# Seymour.net
KiCad netlist of a schematic drawn in EAGLE
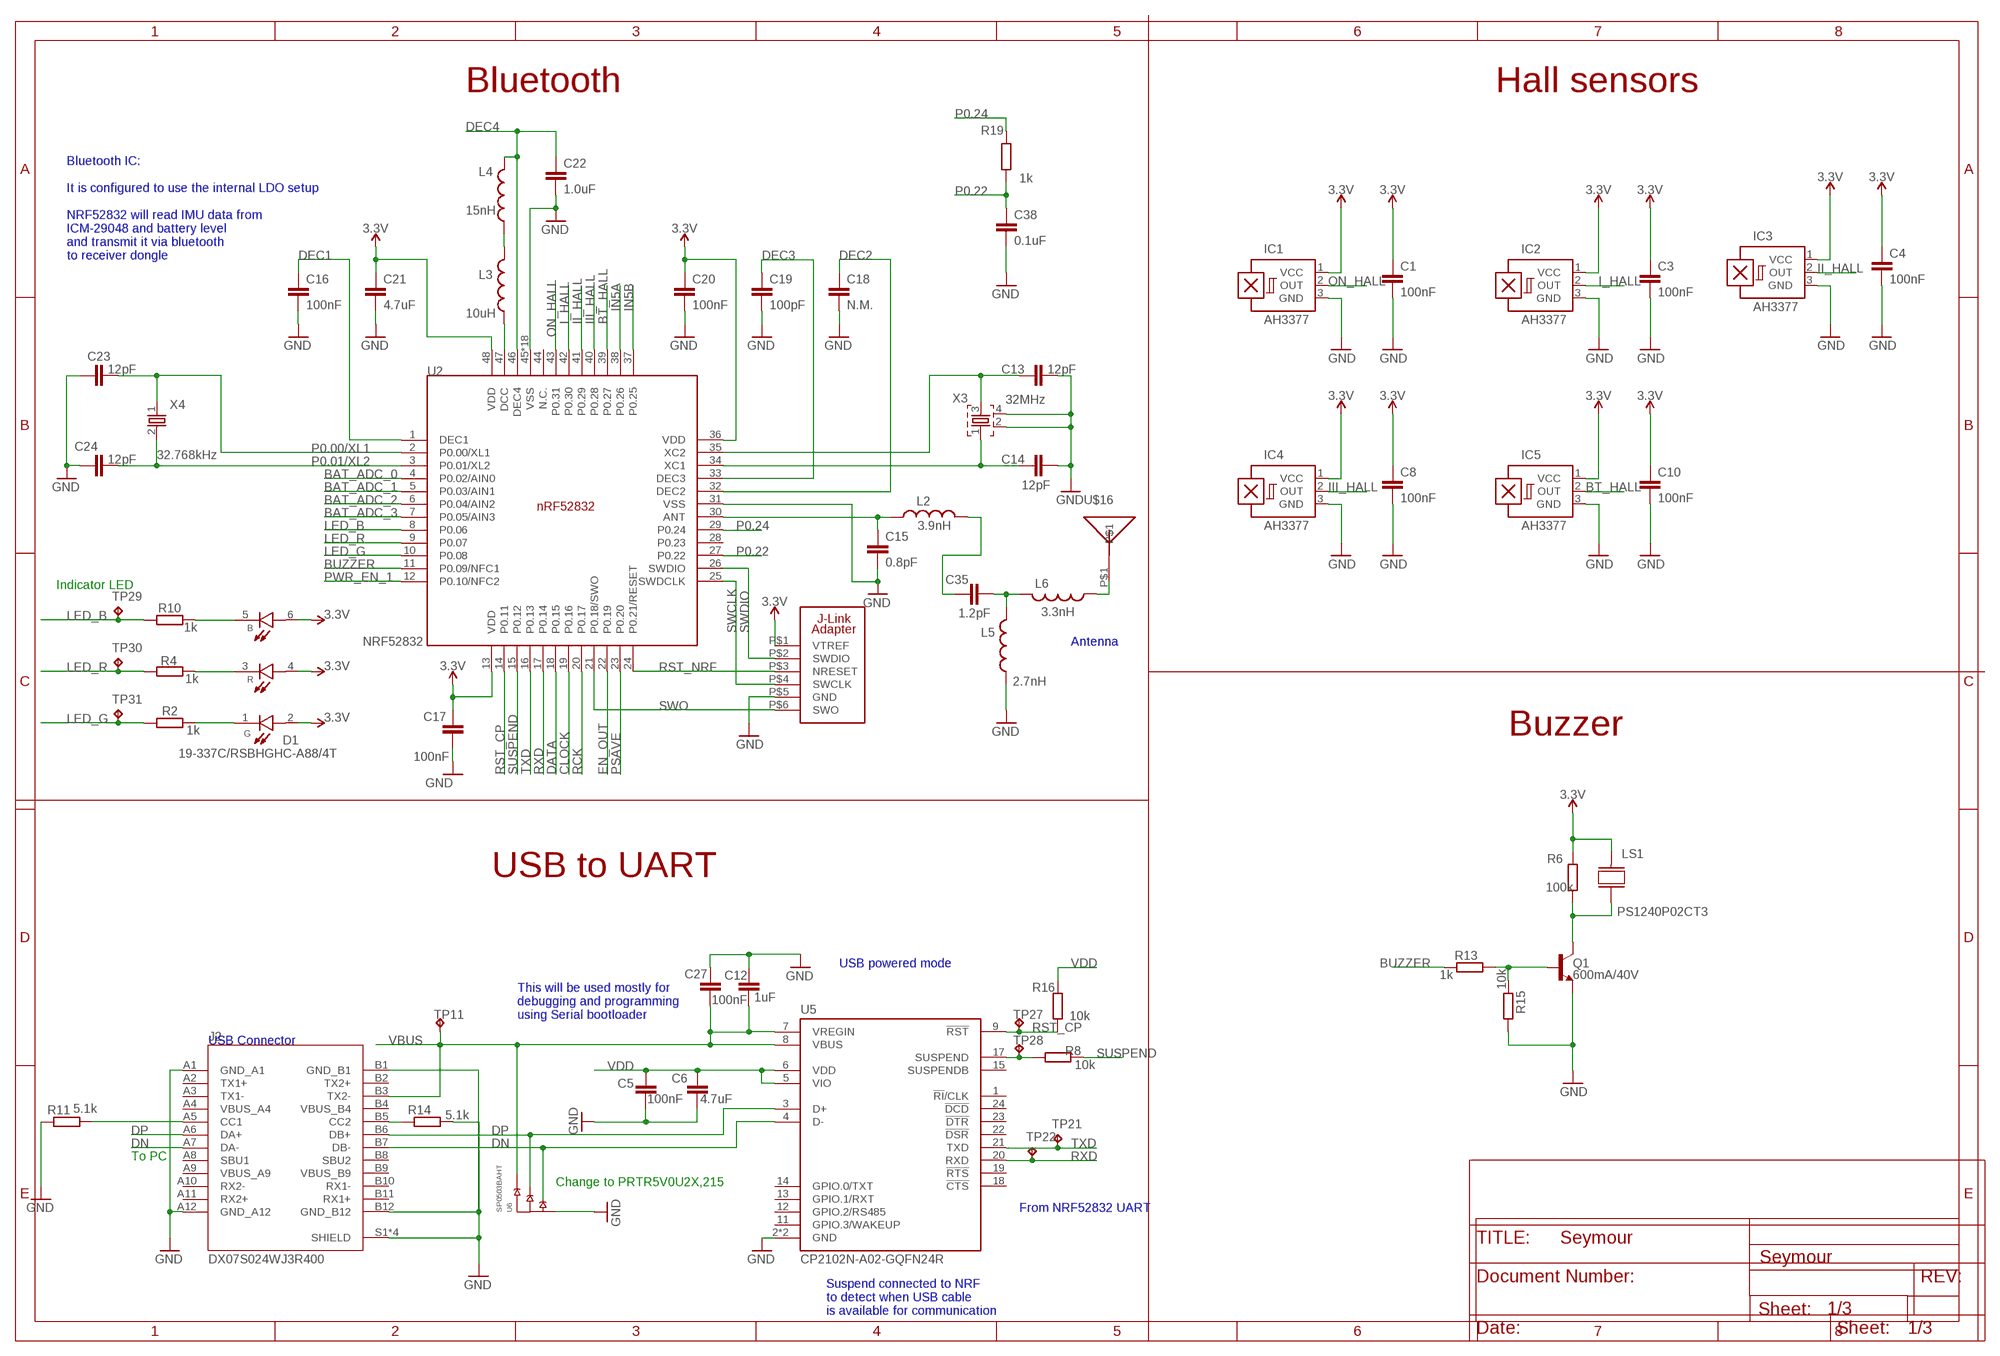
[diagram p0: schematic, sheet 1]
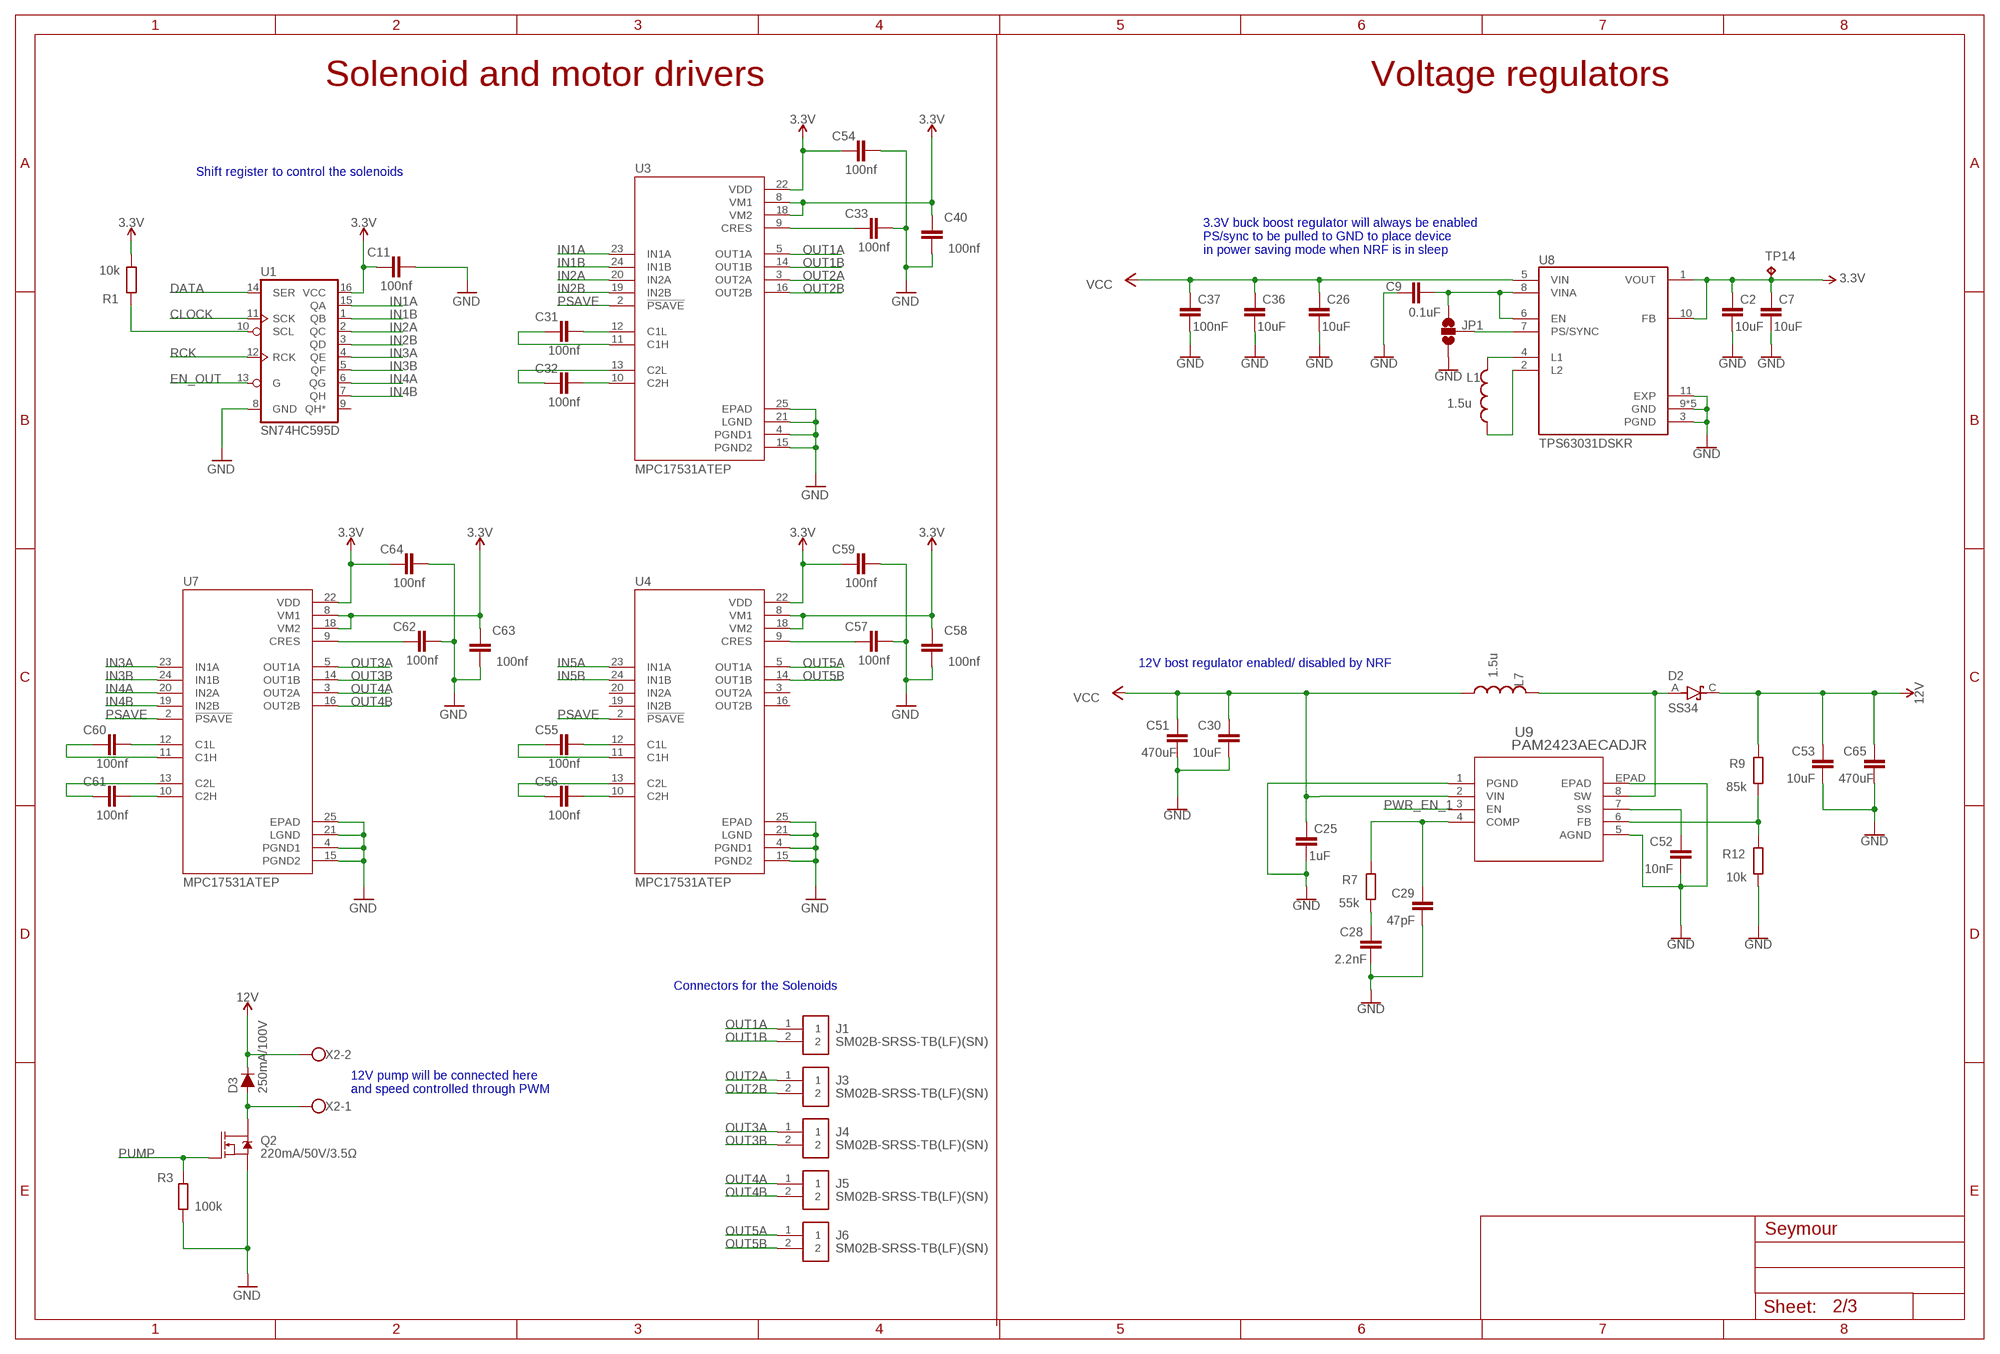
[diagram p1: schematic, sheet 2]
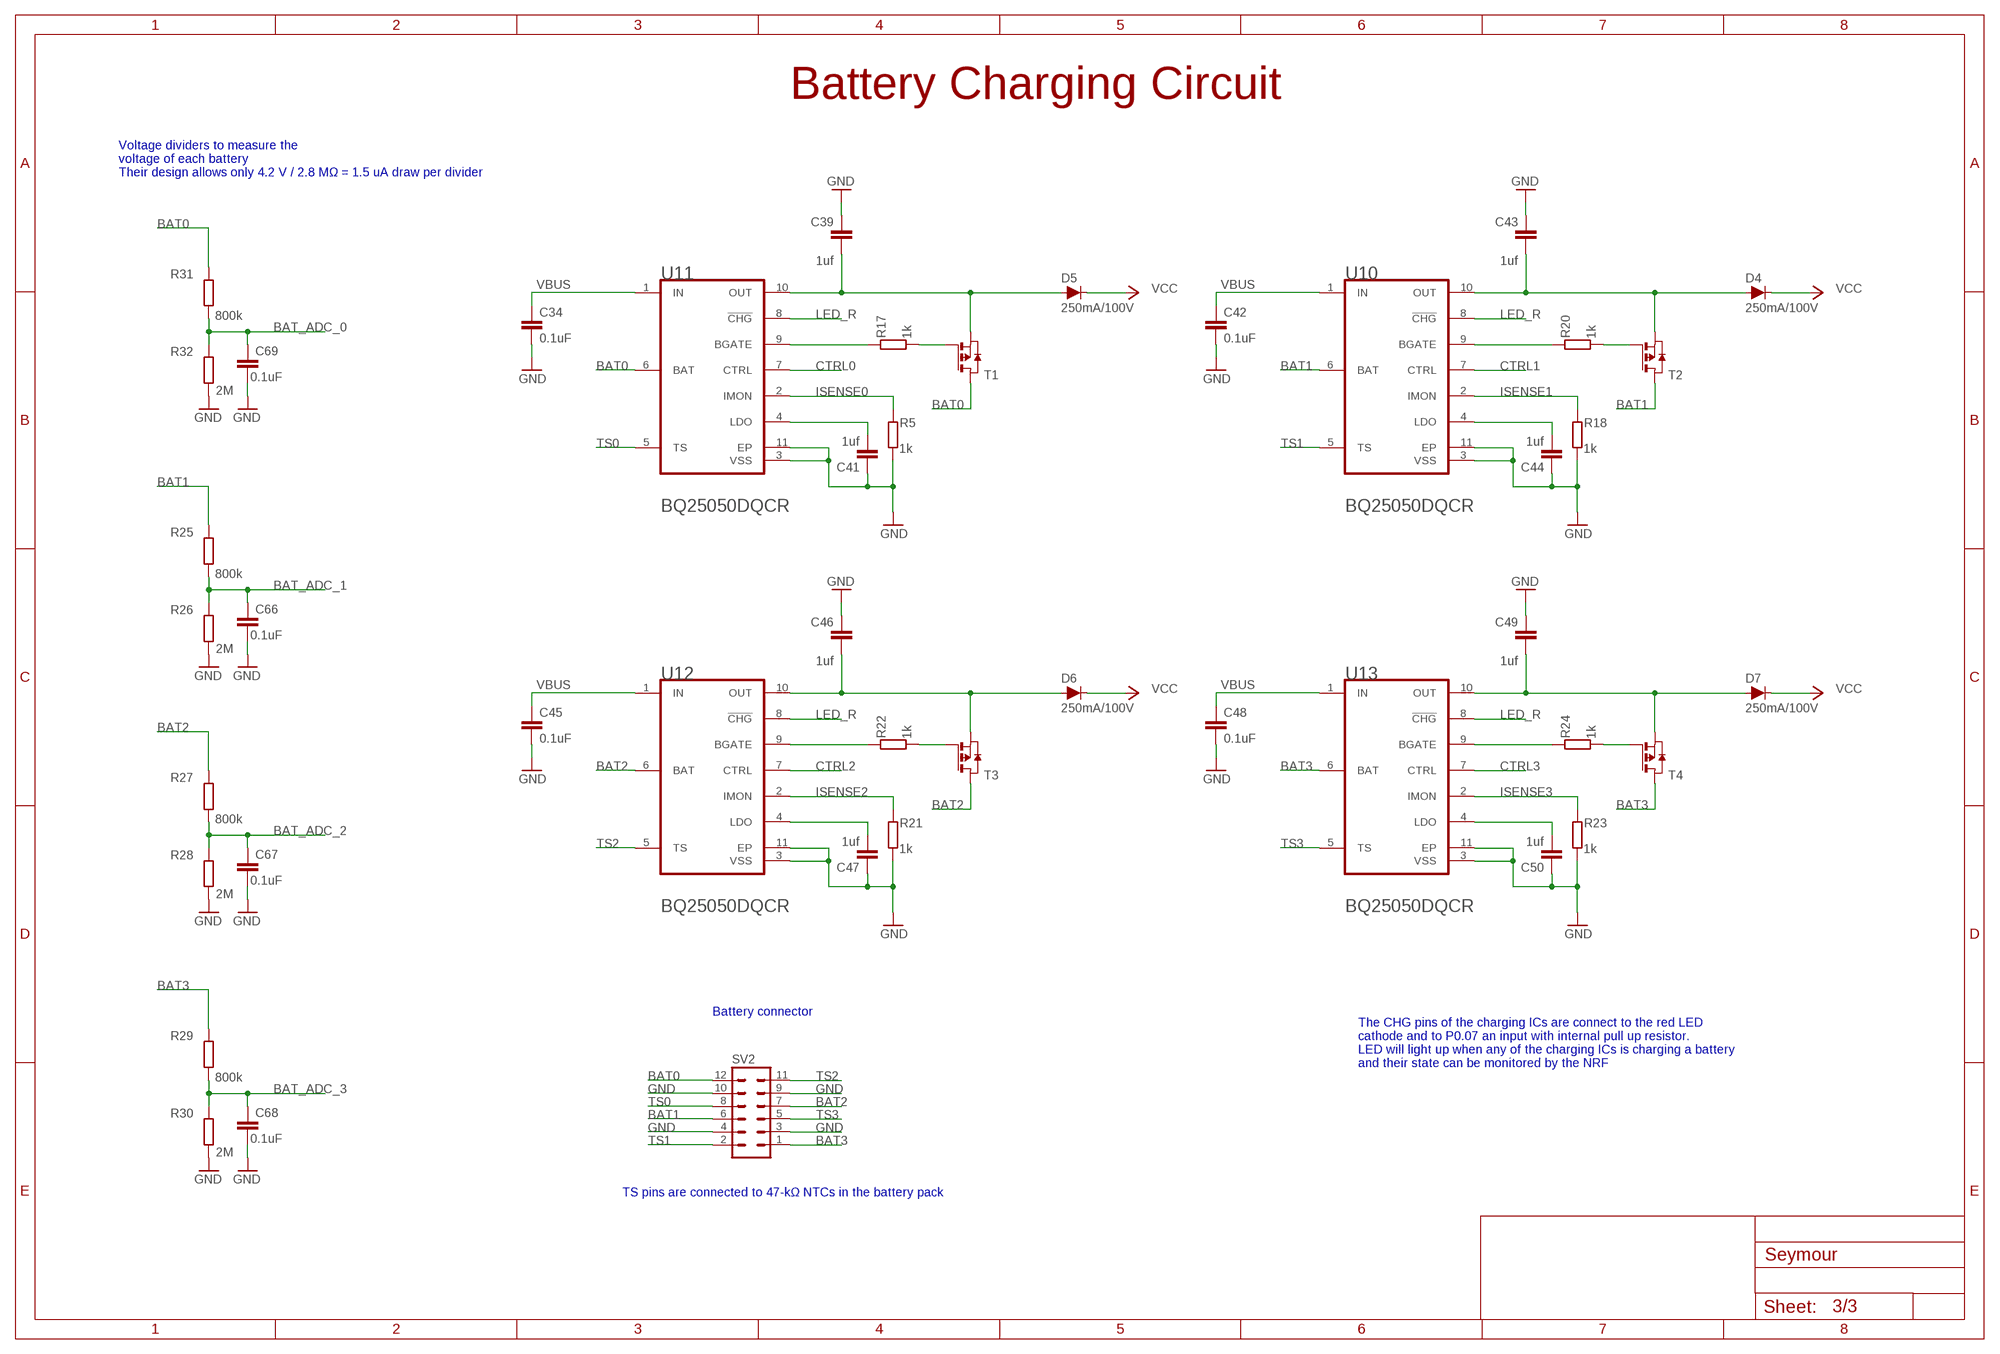
[diagram p2: schematic, sheet 3]

(export (version "E")
  (design (tool "Eeschema 10.0.6"))
  (components
    (comp (ref "C1")
      (value "100nF")
      (footprint "eagle-import:C0402")
      (libsource (lib "eagle-import") (part "C-EUC0402"))
    )
    (comp (ref "C3")
      (value "100nF")
      (footprint "eagle-import:C0402")
      (libsource (lib "eagle-import") (part "C-EUC0402"))
    )
    (comp (ref "C4")
      (value "100nF")
      (footprint "eagle-import:C0402")
      (libsource (lib "eagle-import") (part "C-EUC0402"))
    )
    (comp (ref "C5")
      (value "100nF")
      (footprint "eagle-import:C0402")
      (libsource (lib "eagle-import") (part "resistor_C-EUC0402"))
    )
    (comp (ref "C6")
      (value "4.7uF")
      (footprint "eagle-import:C0603")
      (libsource (lib "eagle-import") (part "resistor_C-EUC0603"))
    )
    (comp (ref "C8")
      (value "100nF")
      (footprint "eagle-import:C0402")
      (libsource (lib "eagle-import") (part "C-EUC0402"))
    )
    (comp (ref "C10")
      (value "100nF")
      (footprint "eagle-import:C0402")
      (libsource (lib "eagle-import") (part "C-EUC0402"))
    )
    (comp (ref "C12")
      (value "1uF")
      (footprint "eagle-import:C0603")
      (libsource (lib "eagle-import") (part "resistor_C-EUC0603"))
    )
    (comp (ref "C13")
      (value "12pF")
      (footprint "eagle-import:C0402")
      (libsource (lib "eagle-import") (part "resistor_C-EUC0402"))
    )
    (comp (ref "C14")
      (value "12pF")
      (footprint "eagle-import:C0402")
      (libsource (lib "eagle-import") (part "resistor_C-EUC0402"))
    )
    (comp (ref "C15")
      (value "0.8pF")
      (footprint "eagle-import:C0402")
      (libsource (lib "eagle-import") (part "resistor_C-EUC0402"))
    )
    (comp (ref "C16")
      (value "100nF")
      (footprint "eagle-import:C0603")
      (libsource (lib "eagle-import") (part "resistor_C-EUC0603"))
    )
    (comp (ref "C17")
      (value "100nF")
      (footprint "eagle-import:C0402")
      (libsource (lib "eagle-import") (part "C-EUC0402"))
    )
    (comp (ref "C18")
      (value "N.M.")
      (footprint "eagle-import:C0603")
      (libsource (lib "eagle-import") (part "resistor_C-EUC0603"))
    )
    (comp (ref "C19")
      (value "100pF")
      (footprint "eagle-import:C0402")
      (libsource (lib "eagle-import") (part "resistor_C-EUC0402"))
    )
    (comp (ref "C20")
      (value "100nF")
      (footprint "eagle-import:C0402")
      (libsource (lib "eagle-import") (part "C-EUC0402"))
    )
    (comp (ref "C21")
      (value "4.7uF")
      (footprint "eagle-import:C0603")
      (libsource (lib "eagle-import") (part "resistor_C-EUC0603"))
    )
    (comp (ref "C22")
      (value "1.0uF")
      (footprint "eagle-import:C0603")
      (libsource (lib "eagle-import") (part "resistor_C-EUC0603"))
    )
    (comp (ref "C23")
      (value "12pF")
      (footprint "eagle-import:C0402")
      (libsource (lib "eagle-import") (part "resistor_C-EUC0402"))
    )
    (comp (ref "C24")
      (value "12pF")
      (footprint "eagle-import:C0402")
      (libsource (lib "eagle-import") (part "resistor_C-EUC0402"))
    )
    (comp (ref "C27")
      (value "100nF")
      (footprint "eagle-import:C0402")
      (libsource (lib "eagle-import") (part "resistor_C-EUC0402"))
    )
    (comp (ref "C35")
      (value "1.2pF")
      (footprint "eagle-import:RESC0402_N")
      (libsource (lib "eagle-import") (part "CAPACITOR_0402_N"))
    )
    (comp (ref "C38")
      (value "0.1uF")
      (footprint "eagle-import:C0402")
      (libsource (lib "eagle-import") (part "resistor_C-EUC0402"))
    )
    (comp (ref "D1")
      (value "19-337C/RSBHGHC-A88/4T")
      (footprint "eagle-import:LED_19-337C_RSBHGHC-A88_4T")
      (fields (field (name "MF") "Everlight Electronics Co Ltd"))
      (libsource (lib "eagle-import") (part "19-337C/RSBHGHC-A88/4T"))
    )
    (comp (ref "IC1")
      (value "AH3377")
      (footprint "eagle-import:SOT23-W")
      (fields (field (name "MF") "ALLEGRO MICROSYSTEMS, INC.") (field (name "MPN") "A1203LLHLT-T"))
      (libsource (lib "eagle-import") (part "A12?LH03"))
    )
    (comp (ref "IC2")
      (value "AH3377")
      (footprint "eagle-import:SOT23-W")
      (fields (field (name "MF") "ALLEGRO MICROSYSTEMS, INC.") (field (name "MPN") "A1203LLHLT-T"))
      (libsource (lib "eagle-import") (part "A12?LH03"))
    )
    (comp (ref "IC3")
      (value "AH3377")
      (footprint "eagle-import:SOT23-W")
      (fields (field (name "MF") "ALLEGRO MICROSYSTEMS, INC.") (field (name "MPN") "A1203LLHLT-T"))
      (libsource (lib "eagle-import") (part "A12?LH03"))
    )
    (comp (ref "IC4")
      (value "AH3377")
      (footprint "eagle-import:SOT23-W")
      (fields (field (name "MF") "ALLEGRO MICROSYSTEMS, INC.") (field (name "MPN") "A1203LLHLT-T"))
      (libsource (lib "eagle-import") (part "A12?LH03"))
    )
    (comp (ref "IC5")
      (value "AH3377")
      (footprint "eagle-import:SOT23-W")
      (fields (field (name "MF") "ALLEGRO MICROSYSTEMS, INC.") (field (name "MPN") "A1203LLHLT-T"))
      (libsource (lib "eagle-import") (part "A12?LH03"))
    )
    (comp (ref "J2")
      (value "DX07S024WJ3R400")
      (footprint "eagle-import:JAE_DX07S024WJ3R400")
      (fields (field (name "DIGI-KEY_PART_NUMBER") "670-2950-1-ND") (field (name "MF") "JAE Electronics"))
      (libsource (lib "eagle-import") (part "DX07S024WJ3R400"))
    )
    (comp (ref "L2")
      (value "3.9nH")
      (footprint "eagle-import:RESC0402_N")
      (libsource (lib "eagle-import") (part "INDUCTOR_0402_N"))
    )
    (comp (ref "L3")
      (value "10uH")
      (footprint "eagle-import:RESC0603_N")
      (libsource (lib "eagle-import") (part "INDUCTOR_0603_N"))
    )
    (comp (ref "L4")
      (value "15nH")
      (footprint "eagle-import:RESC0402_N")
      (libsource (lib "eagle-import") (part "INDUCTOR_0402_N"))
    )
    (comp (ref "L5")
      (value "2.7nH")
      (footprint "eagle-import:RESC0402_N")
      (libsource (lib "eagle-import") (part "INDUCTOR_0402_N"))
    )
    (comp (ref "L6")
      (value "3.3nH")
      (footprint "eagle-import:RESC0402_N")
      (libsource (lib "eagle-import") (part "INDUCTOR_0402_N"))
    )
    (comp (ref "LS1")
      (value "PS1240P02CT3")
      (footprint "eagle-import:XDCR_PS1240P02CT3")
      (fields (field (name "DIGI-KEY_PART_NUMBER") "445-5229-1-ND") (field (name "MF") "TDK"))
      (libsource (lib "eagle-import") (part "PS1240P02CT3"))
    )
    (comp (ref "Q1")
      (value "600mA/40V")
      (footprint "eagle-import:SOT23-3")
      (libsource (lib "eagle-import") (part "TRANS_NPN-MMBT2222AL"))
    )
    (comp (ref "R2")
      (value "1k")
      (footprint "eagle-import:R0402")
      (libsource (lib "eagle-import") (part "resistor_R-EU_R0402"))
    )
    (comp (ref "R4")
      (value "1k")
      (footprint "eagle-import:R0402")
      (libsource (lib "eagle-import") (part "resistor_R-EU_R0402"))
    )
    (comp (ref "R6")
      (value "100k")
      (footprint "eagle-import:R0402")
      (libsource (lib "eagle-import") (part "resistor_R-EU_R0402"))
    )
    (comp (ref "R8")
      (value "10k")
      (footprint "eagle-import:R0402")
      (libsource (lib "eagle-import") (part "resistor_R-EU_R0402"))
    )
    (comp (ref "R10")
      (value "1k")
      (footprint "eagle-import:R0402")
      (libsource (lib "eagle-import") (part "resistor_R-EU_R0402"))
    )
    (comp (ref "R11")
      (value "5.1k")
      (footprint "eagle-import:R0402")
      (libsource (lib "eagle-import") (part "R-EU_R0402"))
    )
    (comp (ref "R13")
      (value "1k")
      (footprint "eagle-import:R0402")
      (libsource (lib "eagle-import") (part "resistor_R-EU_R0402"))
    )
    (comp (ref "R14")
      (value "5.1k")
      (footprint "eagle-import:R0402")
      (libsource (lib "eagle-import") (part "R-EU_R0402"))
    )
    (comp (ref "R15")
      (value "10k")
      (footprint "eagle-import:R0402")
      (libsource (lib "eagle-import") (part "resistor_R-EU_R0402"))
    )
    (comp (ref "R16")
      (value "10k")
      (footprint "eagle-import:R0402")
      (libsource (lib "eagle-import") (part "resistor_R-EU_R0402"))
    )
    (comp (ref "R19")
      (value "1k")
      (footprint "eagle-import:R0402")
      (libsource (lib "eagle-import") (part "R-EU_R0402"))
    )
    (comp (ref "TP11")
      (value "TPTP06R")
      (footprint "eagle-import:TP06R")
      (libsource (lib "eagle-import") (part "TPTP06R"))
    )
    (comp (ref "TP21")
      (value "TPTP06R")
      (footprint "eagle-import:TP06R")
      (libsource (lib "eagle-import") (part "TPTP06R"))
    )
    (comp (ref "TP22")
      (value "TPTP06R")
      (footprint "eagle-import:TP06R")
      (libsource (lib "eagle-import") (part "TPTP06R"))
    )
    (comp (ref "TP27")
      (value "TPTP06R")
      (footprint "eagle-import:TP06R")
      (libsource (lib "eagle-import") (part "TPTP06R"))
    )
    (comp (ref "TP28")
      (value "TPTP06R")
      (footprint "eagle-import:TP06R")
      (libsource (lib "eagle-import") (part "TPTP06R"))
    )
    (comp (ref "TP29")
      (value "TPTP06R")
      (footprint "eagle-import:TP06R")
      (libsource (lib "eagle-import") (part "TPTP06R"))
    )
    (comp (ref "TP30")
      (value "TPTP06R")
      (footprint "eagle-import:TP06R")
      (libsource (lib "eagle-import") (part "TPTP06R"))
    )
    (comp (ref "TP31")
      (value "TPTP06R")
      (footprint "eagle-import:TP06R")
      (libsource (lib "eagle-import") (part "TPTP06R"))
    )
    (comp (ref "U$1")
      (value "J-LINK_6-PIN_ADAPTER-1")
      (footprint "eagle-import:J-LINK_6-PIN_ADAPTER_S")
      (libsource (lib "eagle-import") (part "J-LINK_6-PIN_ADAPTER-1"))
    )
    (comp (ref "U$16")
      (value "ANT_2450AT18B100E")
      (footprint "eagle-import:2450AT18B100E")
      (libsource (lib "eagle-import") (part "ANT_2450AT18B100E"))
    )
    (comp (ref "U2")
      (value "NRF52832")
      (footprint "eagle-import:QFN40P600X600X90-48_N")
      (libsource (lib "eagle-import") (part "NRF52832"))
    )
    (comp (ref "U5")
      (value "CP2102N-A02-GQFN24R")
      (footprint "eagle-import:QFN50P400X400X80-25N")
      (fields (field (name "MF") "Silicon Labs"))
      (libsource (lib "eagle-import") (part "CP2102N-A02-GQFN24R"))
    )
    (comp (ref "U6")
      (value "SP0503BAHT")
      (footprint "eagle-import:SOT143")
      (fields (field (name "MF") "Littelfuse Inc."))
      (libsource (lib "eagle-import") (part "SP0503BAHT"))
    )
    (comp (ref "X3")
      (value "32MHz")
      (footprint "eagle-import:BT-XTAL_2016_N")
      (libsource (lib "eagle-import") (part "XTAL_32MHZ"))
    )
    (comp (ref "X4")
      (value "32.768kHz")
      (footprint "eagle-import:XTAL_3215_N")
      (libsource (lib "eagle-import") (part "XTAL_32KHZ"))
    )
    (comp (ref "C34")
      (value "0.1uF")
      (footprint "eagle-import:C0402")
      (libsource (lib "eagle-import") (part "C-EUC0402"))
    )
    (comp (ref "C39")
      (value "1uf")
      (footprint "eagle-import:C0402")
      (libsource (lib "eagle-import") (part "C-EUC0402"))
    )
    (comp (ref "C41")
      (value "1uf")
      (footprint "eagle-import:C0402")
      (libsource (lib "eagle-import") (part "C-EUC0402"))
    )
    (comp (ref "C42")
      (value "0.1uF")
      (footprint "eagle-import:C0402")
      (libsource (lib "eagle-import") (part "C-EUC0402"))
    )
    (comp (ref "C43")
      (value "1uf")
      (footprint "eagle-import:C0402")
      (libsource (lib "eagle-import") (part "C-EUC0402"))
    )
    (comp (ref "C44")
      (value "1uf")
      (footprint "eagle-import:C0402")
      (libsource (lib "eagle-import") (part "C-EUC0402"))
    )
    (comp (ref "C45")
      (value "0.1uF")
      (footprint "eagle-import:C0402")
      (libsource (lib "eagle-import") (part "C-EUC0402"))
    )
    (comp (ref "C46")
      (value "1uf")
      (footprint "eagle-import:C0402")
      (libsource (lib "eagle-import") (part "C-EUC0402"))
    )
    (comp (ref "C47")
      (value "1uf")
      (footprint "eagle-import:C0402")
      (libsource (lib "eagle-import") (part "C-EUC0402"))
    )
    (comp (ref "C48")
      (value "0.1uF")
      (footprint "eagle-import:C0402")
      (libsource (lib "eagle-import") (part "C-EUC0402"))
    )
    (comp (ref "C49")
      (value "1uf")
      (footprint "eagle-import:C0402")
      (libsource (lib "eagle-import") (part "C-EUC0402"))
    )
    (comp (ref "C50")
      (value "1uf")
      (footprint "eagle-import:C0402")
      (libsource (lib "eagle-import") (part "C-EUC0402"))
    )
    (comp (ref "C66")
      (value "0.1uF")
      (footprint "eagle-import:C0402")
      (libsource (lib "eagle-import") (part "C-EUC0402"))
    )
    (comp (ref "C67")
      (value "0.1uF")
      (footprint "eagle-import:C0402")
      (libsource (lib "eagle-import") (part "C-EUC0402"))
    )
    (comp (ref "C68")
      (value "0.1uF")
      (footprint "eagle-import:C0402")
      (libsource (lib "eagle-import") (part "C-EUC0402"))
    )
    (comp (ref "C69")
      (value "0.1uF")
      (footprint "eagle-import:C0402")
      (libsource (lib "eagle-import") (part "C-EUC0402"))
    )
    (comp (ref "D4")
      (value "250mA/100V")
      (footprint "eagle-import:SOD-323")
      (libsource (lib "eagle-import") (part "DIODE-BAS16J"))
    )
    (comp (ref "D5")
      (value "250mA/100V")
      (footprint "eagle-import:SOD-323")
      (libsource (lib "eagle-import") (part "DIODE-BAS16J"))
    )
    (comp (ref "D6")
      (value "250mA/100V")
      (footprint "eagle-import:SOD-323")
      (libsource (lib "eagle-import") (part "DIODE-BAS16J"))
    )
    (comp (ref "D7")
      (value "250mA/100V")
      (footprint "eagle-import:SOD-323")
      (libsource (lib "eagle-import") (part "DIODE-BAS16J"))
    )
    (comp (ref "R5")
      (value "1k")
      (footprint "eagle-import:R0402")
      (libsource (lib "eagle-import") (part "R-EU_R0402"))
    )
    (comp (ref "R17")
      (value "1k")
      (footprint "eagle-import:R0402")
      (libsource (lib "eagle-import") (part "R-EU_R0402"))
    )
    (comp (ref "R18")
      (value "1k")
      (footprint "eagle-import:R0402")
      (libsource (lib "eagle-import") (part "R-EU_R0402"))
    )
    (comp (ref "R20")
      (value "1k")
      (footprint "eagle-import:R0402")
      (libsource (lib "eagle-import") (part "R-EU_R0402"))
    )
    (comp (ref "R21")
      (value "1k")
      (footprint "eagle-import:R0402")
      (libsource (lib "eagle-import") (part "R-EU_R0402"))
    )
    (comp (ref "R22")
      (value "1k")
      (footprint "eagle-import:R0402")
      (libsource (lib "eagle-import") (part "R-EU_R0402"))
    )
    (comp (ref "R23")
      (value "1k")
      (footprint "eagle-import:R0402")
      (libsource (lib "eagle-import") (part "R-EU_R0402"))
    )
    (comp (ref "R24")
      (value "1k")
      (footprint "eagle-import:R0402")
      (libsource (lib "eagle-import") (part "R-EU_R0402"))
    )
    (comp (ref "R25")
      (value "800k")
      (footprint "eagle-import:R0402")
      (libsource (lib "eagle-import") (part "resistor_R-EU_R0402"))
    )
    (comp (ref "R26")
      (value "2M")
      (footprint "eagle-import:R0402")
      (libsource (lib "eagle-import") (part "resistor_R-EU_R0402"))
    )
    (comp (ref "R27")
      (value "800k")
      (footprint "eagle-import:R0402")
      (libsource (lib "eagle-import") (part "resistor_R-EU_R0402"))
    )
    (comp (ref "R28")
      (value "2M")
      (footprint "eagle-import:R0402")
      (libsource (lib "eagle-import") (part "resistor_R-EU_R0402"))
    )
    (comp (ref "R29")
      (value "800k")
      (footprint "eagle-import:R0402")
      (libsource (lib "eagle-import") (part "resistor_R-EU_R0402"))
    )
    (comp (ref "R30")
      (value "2M")
      (footprint "eagle-import:R0402")
      (libsource (lib "eagle-import") (part "resistor_R-EU_R0402"))
    )
    (comp (ref "R31")
      (value "800k")
      (footprint "eagle-import:R0402")
      (libsource (lib "eagle-import") (part "resistor_R-EU_R0402"))
    )
    (comp (ref "R32")
      (value "2M")
      (footprint "eagle-import:R0402")
      (libsource (lib "eagle-import") (part "resistor_R-EU_R0402"))
    )
    (comp (ref "SV2")
      (value "MA06-2")
      (footprint "eagle-import:MA06-2")
      (libsource (lib "eagle-import") (part "MA06-2"))
    )
    (comp (ref "T1")
      (value "PMOSSOT23")
      (footprint "eagle-import:SOT-23")
      (libsource (lib "eagle-import") (part "PMOSSOT23"))
    )
    (comp (ref "T2")
      (value "PMOSSOT23")
      (footprint "eagle-import:SOT-23")
      (libsource (lib "eagle-import") (part "PMOSSOT23"))
    )
    (comp (ref "T3")
      (value "PMOSSOT23")
      (footprint "eagle-import:SOT-23")
      (libsource (lib "eagle-import") (part "PMOSSOT23"))
    )
    (comp (ref "T4")
      (value "PMOSSOT23")
      (footprint "eagle-import:SOT-23")
      (libsource (lib "eagle-import") (part "PMOSSOT23"))
    )
    (comp (ref "U10")
      (value "TEXAS_INSTRUMENTS_BQ25050DQCRTEXAS_INSTRUMENTS_BQ25050DQCR_0_0")
      (footprint "eagle-import:TEXAS_INSTRUMENTS_BQ25050DQCR_0")
      (fields (field (name "MF") "Texas Instruments") (field (name "MPN") "BQ25050DQCR"))
      (libsource (lib "eagle-import") (part "TEXAS_INSTRUMENTS_BQ25050DQCRTEXAS_INSTRUMENTS_BQ25050DQCR_0_0"))
    )
    (comp (ref "U11")
      (value "TEXAS_INSTRUMENTS_BQ25050DQCRTEXAS_INSTRUMENTS_BQ25050DQCR_0_0")
      (footprint "eagle-import:TEXAS_INSTRUMENTS_BQ25050DQCR_0")
      (fields (field (name "MF") "Texas Instruments") (field (name "MPN") "BQ25050DQCR"))
      (libsource (lib "eagle-import") (part "TEXAS_INSTRUMENTS_BQ25050DQCRTEXAS_INSTRUMENTS_BQ25050DQCR_0_0"))
    )
    (comp (ref "U12")
      (value "TEXAS_INSTRUMENTS_BQ25050DQCRTEXAS_INSTRUMENTS_BQ25050DQCR_0_0")
      (footprint "eagle-import:TEXAS_INSTRUMENTS_BQ25050DQCR_0")
      (fields (field (name "MF") "Texas Instruments") (field (name "MPN") "BQ25050DQCR"))
      (libsource (lib "eagle-import") (part "TEXAS_INSTRUMENTS_BQ25050DQCRTEXAS_INSTRUMENTS_BQ25050DQCR_0_0"))
    )
    (comp (ref "U13")
      (value "TEXAS_INSTRUMENTS_BQ25050DQCRTEXAS_INSTRUMENTS_BQ25050DQCR_0_0")
      (footprint "eagle-import:TEXAS_INSTRUMENTS_BQ25050DQCR_0")
      (fields (field (name "MF") "Texas Instruments") (field (name "MPN") "BQ25050DQCR"))
      (libsource (lib "eagle-import") (part "TEXAS_INSTRUMENTS_BQ25050DQCRTEXAS_INSTRUMENTS_BQ25050DQCR_0_0"))
    )
    (comp (ref "C2")
      (value "10uF")
      (footprint "eagle-import:C0603")
      (libsource (lib "eagle-import") (part "resistor_C-EUC0603"))
    )
    (comp (ref "C7")
      (value "10uF")
      (footprint "eagle-import:C0603")
      (libsource (lib "eagle-import") (part "resistor_C-EUC0603"))
    )
    (comp (ref "C9")
      (value "0.1uF")
      (footprint "eagle-import:C0603")
      (libsource (lib "eagle-import") (part "resistor_C-EUC0603"))
    )
    (comp (ref "C11")
      (value "100nf")
      (footprint "eagle-import:RESC0402_N")
      (libsource (lib "eagle-import") (part "CAPACITOR_0402_N"))
    )
    (comp (ref "C25")
      (value "1uF")
      (footprint "eagle-import:C0603")
      (libsource (lib "eagle-import") (part "resistor_C-EUC0603"))
    )
    (comp (ref "C26")
      (value "10uF")
      (footprint "eagle-import:C0603")
      (libsource (lib "eagle-import") (part "resistor_C-EUC0603"))
    )
    (comp (ref "C28")
      (value "2.2nF")
      (footprint "eagle-import:C0603")
      (libsource (lib "eagle-import") (part "resistor_C-EUC0603"))
    )
    (comp (ref "C29")
      (value "47pF")
      (footprint "eagle-import:C0603")
      (libsource (lib "eagle-import") (part "resistor_C-EUC0603"))
    )
    (comp (ref "C30")
      (value "10uF")
      (footprint "eagle-import:C0603")
      (libsource (lib "eagle-import") (part "resistor_C-EUC0603"))
    )
    (comp (ref "C31")
      (value "100nf")
      (footprint "eagle-import:RESC0402_N")
      (libsource (lib "eagle-import") (part "CAPACITOR_0402_N"))
    )
    (comp (ref "C32")
      (value "100nf")
      (footprint "eagle-import:RESC0402_N")
      (libsource (lib "eagle-import") (part "CAPACITOR_0402_N"))
    )
    (comp (ref "C33")
      (value "100nf")
      (footprint "eagle-import:RESC0402_N")
      (libsource (lib "eagle-import") (part "CAPACITOR_0402_N"))
    )
    (comp (ref "C36")
      (value "10uF")
      (footprint "eagle-import:C0603")
      (libsource (lib "eagle-import") (part "resistor_C-EUC0603"))
    )
    (comp (ref "C37")
      (value "100nF")
      (footprint "eagle-import:C0603")
      (libsource (lib "eagle-import") (part "resistor_C-EUC0603"))
    )
    (comp (ref "C40")
      (value "100nf")
      (footprint "eagle-import:RESC0402_N")
      (libsource (lib "eagle-import") (part "CAPACITOR_0402_N"))
    )
    (comp (ref "C51")
      (value "470uF")
      (footprint "eagle-import:C0603")
      (libsource (lib "eagle-import") (part "resistor_C-EUC0603"))
    )
    (comp (ref "C52")
      (value "10nF")
      (footprint "eagle-import:C0603")
      (libsource (lib "eagle-import") (part "resistor_C-EUC0603"))
    )
    (comp (ref "C53")
      (value "10uF")
      (footprint "eagle-import:C0603")
      (libsource (lib "eagle-import") (part "resistor_C-EUC0603"))
    )
    (comp (ref "C54")
      (value "100nf")
      (footprint "eagle-import:RESC0402_N")
      (libsource (lib "eagle-import") (part "CAPACITOR_0402_N"))
    )
    (comp (ref "C55")
      (value "100nf")
      (footprint "eagle-import:RESC0402_N")
      (libsource (lib "eagle-import") (part "CAPACITOR_0402_N"))
    )
    (comp (ref "C56")
      (value "100nf")
      (footprint "eagle-import:RESC0402_N")
      (libsource (lib "eagle-import") (part "CAPACITOR_0402_N"))
    )
    (comp (ref "C57")
      (value "100nf")
      (footprint "eagle-import:RESC0402_N")
      (libsource (lib "eagle-import") (part "CAPACITOR_0402_N"))
    )
    (comp (ref "C58")
      (value "100nf")
      (footprint "eagle-import:RESC0402_N")
      (libsource (lib "eagle-import") (part "CAPACITOR_0402_N"))
    )
    (comp (ref "C59")
      (value "100nf")
      (footprint "eagle-import:RESC0402_N")
      (libsource (lib "eagle-import") (part "CAPACITOR_0402_N"))
    )
    (comp (ref "C60")
      (value "100nf")
      (footprint "eagle-import:RESC0402_N")
      (libsource (lib "eagle-import") (part "CAPACITOR_0402_N"))
    )
    (comp (ref "C61")
      (value "100nf")
      (footprint "eagle-import:RESC0402_N")
      (libsource (lib "eagle-import") (part "CAPACITOR_0402_N"))
    )
    (comp (ref "C62")
      (value "100nf")
      (footprint "eagle-import:RESC0402_N")
      (libsource (lib "eagle-import") (part "CAPACITOR_0402_N"))
    )
    (comp (ref "C63")
      (value "100nf")
      (footprint "eagle-import:RESC0402_N")
      (libsource (lib "eagle-import") (part "CAPACITOR_0402_N"))
    )
    (comp (ref "C64")
      (value "100nf")
      (footprint "eagle-import:RESC0402_N")
      (libsource (lib "eagle-import") (part "CAPACITOR_0402_N"))
    )
    (comp (ref "C65")
      (value "470uF")
      (footprint "eagle-import:C0603")
      (libsource (lib "eagle-import") (part "resistor_C-EUC0603"))
    )
    (comp (ref "D2")
      (value "SS34")
      (footprint "eagle-import:DIOM7959X265N")
      (fields (field (name "MF") "ON Semiconductor"))
      (libsource (lib "eagle-import") (part "SS34"))
    )
    (comp (ref "D3")
      (value "250mA/100V")
      (footprint "eagle-import:SOD-323")
      (libsource (lib "eagle-import") (part "DIODE-BAS16J"))
    )
    (comp (ref "J1")
      (value "SM02B-SRSS-TB(LF)(SN)")
      (footprint "eagle-import:SM02B-SRSS-TB(LF)(SN)")
      (fields (field (name "MF") "JST Sales") (field (name "MP") "SM02B-SRSS-TB_LF__SN_"))
      (libsource (lib "eagle-import") (part "SM02B-SRSS-TB(LF)(SN)"))
    )
    (comp (ref "J3")
      (value "SM02B-SRSS-TB(LF)(SN)")
      (footprint "eagle-import:SM02B-SRSS-TB(LF)(SN)")
      (fields (field (name "MF") "JST Sales") (field (name "MP") "SM02B-SRSS-TB_LF__SN_"))
      (libsource (lib "eagle-import") (part "SM02B-SRSS-TB(LF)(SN)"))
    )
    (comp (ref "J4")
      (value "SM02B-SRSS-TB(LF)(SN)")
      (footprint "eagle-import:SM02B-SRSS-TB(LF)(SN)")
      (fields (field (name "MF") "JST Sales") (field (name "MP") "SM02B-SRSS-TB_LF__SN_"))
      (libsource (lib "eagle-import") (part "SM02B-SRSS-TB(LF)(SN)"))
    )
    (comp (ref "J5")
      (value "SM02B-SRSS-TB(LF)(SN)")
      (footprint "eagle-import:SM02B-SRSS-TB(LF)(SN)")
      (fields (field (name "MF") "JST Sales") (field (name "MP") "SM02B-SRSS-TB_LF__SN_"))
      (libsource (lib "eagle-import") (part "SM02B-SRSS-TB(LF)(SN)"))
    )
    (comp (ref "J6")
      (value "SM02B-SRSS-TB(LF)(SN)")
      (footprint "eagle-import:SM02B-SRSS-TB(LF)(SN)")
      (fields (field (name "MF") "JST Sales") (field (name "MP") "SM02B-SRSS-TB_LF__SN_"))
      (libsource (lib "eagle-import") (part "SM02B-SRSS-TB(LF)(SN)"))
    )
    (comp (ref "JP1")
      (value "SPARKFUN-JUMPERS_JUMPER-SMT_NC")
      (footprint "eagle-import:SPARKFUN-JUMPERS_SMT-JUMPER_TRACE_SILK")
      (libsource (lib "eagle-import") (part "SPARKFUN-JUMPERS_JUMPER-SMT_NC"))
    )
    (comp (ref "L1")
      (value "1.5u")
      (footprint "eagle-import:XFL4020")
      (libsource (lib "eagle-import") (part "XFL4020"))
    )
    (comp (ref "L7")
      (value "1.5u")
      (footprint "eagle-import:XFL4020")
      (libsource (lib "eagle-import") (part "XFL4020"))
    )
    (comp (ref "Q2")
      (value "220mA/50V/3.5Ω")
      (footprint "eagle-import:SOT23-3")
      (libsource (lib "eagle-import") (part "MOSFET-NCH-BSS138"))
    )
    (comp (ref "R1")
      (value "10k")
      (footprint "eagle-import:R0402")
      (libsource (lib "eagle-import") (part "resistor_R-EU_R0402"))
    )
    (comp (ref "R3")
      (value "100k")
      (footprint "eagle-import:R0402")
      (libsource (lib "eagle-import") (part "resistor_R-EU_R0402"))
    )
    (comp (ref "R7")
      (value "55k")
      (footprint "eagle-import:R0402")
      (libsource (lib "eagle-import") (part "resistor_R-EU_R0402"))
    )
    (comp (ref "R9")
      (value "85k")
      (footprint "eagle-import:R0402")
      (libsource (lib "eagle-import") (part "resistor_R-EU_R0402"))
    )
    (comp (ref "R12")
      (value "10k")
      (footprint "eagle-import:R0402")
      (libsource (lib "eagle-import") (part "resistor_R-EU_R0402"))
    )
    (comp (ref "TP14")
      (value "TPTP06R")
      (footprint "eagle-import:TP06R")
      (libsource (lib "eagle-import") (part "TPTP06R"))
    )
    (comp (ref "U1")
      (value "SN74HC595D")
      (footprint "eagle-import:SO16")
      (libsource (lib "eagle-import") (part "74595DHC"))
    )
    (comp (ref "U3")
      (value "MPC17531ATEP")
      (footprint "eagle-import:QFN50P400X400X100-25N")
      (fields (field (name "MF") "NXP Semiconductors"))
      (libsource (lib "eagle-import") (part "MPC17531ATEP"))
    )
    (comp (ref "U4")
      (value "MPC17531ATEP")
      (footprint "eagle-import:QFN50P400X400X100-25N")
      (fields (field (name "MF") "NXP Semiconductors"))
      (libsource (lib "eagle-import") (part "MPC17531ATEP"))
    )
    (comp (ref "U7")
      (value "MPC17531ATEP")
      (footprint "eagle-import:QFN50P400X400X100-25N")
      (fields (field (name "MF") "NXP Semiconductors"))
      (libsource (lib "eagle-import") (part "MPC17531ATEP"))
    )
    (comp (ref "U8")
      (value "TPS63031DSKR")
      (footprint "eagle-import:SON50P250X250X80-11N")
      (fields (field (name "MF") "Texas Instruments"))
      (libsource (lib "eagle-import") (part "TPS63031DSKR"))
    )
    (comp (ref "U9")
      (value "PAM2423AECADJR")
      (footprint "eagle-import:SOP-8_PAM2423AECADJR_DIO")
      (fields (field (name "COPYRIGHT") "Copyright (C) 2021 Ultra Librarian. All rights reserved."))
      (libsource (lib "eagle-import") (part "PAM2423AECADJR"))
    )
    (comp (ref "X2")
      (value "W237-102")
      (footprint "eagle-import:W237-102")
      (fields (field (name "MPN") "237-102"))
      (libsource (lib "eagle-import") (part "W237-102"))
    )
  )
  (nets
    (net (code "1") (name "3.3V") (class "Default")
      (node (ref "C1") (pin "1") (pinfunction "1_1") (pintype "passive"))
      (node (ref "C10") (pin "1") (pinfunction "1_1") (pintype "passive"))
      (node (ref "C11") (pin "2") (pinfunction "2_2") (pintype "passive"))
      (node (ref "C17") (pin "1") (pinfunction "1_1") (pintype "passive"))
      (node (ref "C2") (pin "1") (pinfunction "1_1") (pintype "passive"))
      (node (ref "C20") (pin "1") (pinfunction "1_1") (pintype "passive"))
      (node (ref "C21") (pin "1") (pinfunction "1_1") (pintype "passive"))
      (node (ref "C3") (pin "1") (pinfunction "1_1") (pintype "passive"))
      (node (ref "C4") (pin "1") (pinfunction "1_1") (pintype "passive"))
      (node (ref "C40") (pin "1") (pinfunction "1_1") (pintype "passive"))
      (node (ref "C54") (pin "2") (pinfunction "2_2") (pintype "passive"))
      (node (ref "C58") (pin "1") (pinfunction "1_1") (pintype "passive"))
      (node (ref "C59") (pin "2") (pinfunction "2_2") (pintype "passive"))
      (node (ref "C63") (pin "1") (pinfunction "1_1") (pintype "passive"))
      (node (ref "C64") (pin "2") (pinfunction "2_2") (pintype "passive"))
      (node (ref "C7") (pin "1") (pinfunction "1_1") (pintype "passive"))
      (node (ref "C8") (pin "1") (pinfunction "1_1") (pintype "passive"))
      (node (ref "D1") (pin "2") (pinfunction "G_A_2") (pintype "passive"))
      (node (ref "D1") (pin "4") (pinfunction "R_A_4") (pintype "passive"))
      (node (ref "D1") (pin "6") (pinfunction "B_A_6") (pintype "passive"))
      (node (ref "IC1") (pin "1") (pinfunction "VCC_1") (pintype "power_in"))
      (node (ref "IC2") (pin "1") (pinfunction "VCC_1") (pintype "power_in"))
      (node (ref "IC3") (pin "1") (pinfunction "VCC_1") (pintype "power_in"))
      (node (ref "IC4") (pin "1") (pinfunction "VCC_1") (pintype "power_in"))
      (node (ref "IC5") (pin "1") (pinfunction "VCC_1") (pintype "power_in"))
      (node (ref "LS1") (pin "2") (pinfunction "2_2") (pintype "passive"))
      (node (ref "R1") (pin "2") (pinfunction "2_2") (pintype "passive"))
      (node (ref "R6") (pin "1") (pinfunction "1_1") (pintype "passive"))
      (node (ref "TP14") (pin "TP") (pinfunction "TP_TP") (pintype "input"))
      (node (ref "U$1") (pin "P$1") (pinfunction "VTREF_P$1") (pintype "bidirectional"))
      (node (ref "U1") (pin "16") (pinfunction "VCC_16") (pintype "power_in"))
      (node (ref "U2") (pin "13") (pinfunction "VDD_13") (pintype "power_in"))
      (node (ref "U2") (pin "36") (pinfunction "VDD_36") (pintype "power_in"))
      (node (ref "U2") (pin "48") (pinfunction "VDD_48") (pintype "power_in"))
      (node (ref "U3") (pin "18") (pinfunction "VM2_18") (pintype "power_in"))
      (node (ref "U3") (pin "22") (pinfunction "VDD_22") (pintype "power_in"))
      (node (ref "U3") (pin "8") (pinfunction "VM1_8") (pintype "power_in"))
      (node (ref "U4") (pin "18") (pinfunction "VM2_18") (pintype "power_in"))
      (node (ref "U4") (pin "22") (pinfunction "VDD_22") (pintype "power_in"))
      (node (ref "U4") (pin "8") (pinfunction "VM1_8") (pintype "power_in"))
      (node (ref "U7") (pin "18") (pinfunction "VM2_18") (pintype "power_in"))
      (node (ref "U7") (pin "22") (pinfunction "VDD_22") (pintype "power_in"))
      (node (ref "U7") (pin "8") (pinfunction "VM1_8") (pintype "power_in"))
      (node (ref "U8") (pin "1") (pinfunction "VOUT_1") (pintype "output"))
      (node (ref "U8") (pin "10") (pinfunction "FB_10") (pintype "input"))
    )
    (net (code "2") (name "12V") (class "Default")
      (node (ref "C53") (pin "1") (pinfunction "1_1") (pintype "passive"))
      (node (ref "C65") (pin "1") (pinfunction "1_1") (pintype "passive"))
      (node (ref "D2") (pin "C") (pinfunction "K_C") (pintype "passive"))
      (node (ref "D3") (pin "C") (pinfunction "C_C") (pintype "passive"))
      (node (ref "R9") (pin "2") (pinfunction "2_2") (pintype "passive"))
      (node (ref "X2") (pin "2") (pinfunction "KL_2") (pintype "passive"))
    )
    (net (code "3") (name "BAT0") (class "Default")
      (node (ref "R31") (pin "2") (pinfunction "2_2") (pintype "passive"))
      (node (ref "SV2") (pin "12") (pinfunction "12_12") (pintype "passive"))
      (node (ref "T1") (pin "1") (pinfunction "D_1") (pintype "passive"))
      (node (ref "U11") (pin "6") (pinfunction "BAT_6") (pintype "bidirectional"))
    )
    (net (code "4") (name "BAT1") (class "Default")
      (node (ref "R25") (pin "2") (pinfunction "2_2") (pintype "passive"))
      (node (ref "SV2") (pin "6") (pinfunction "6_6") (pintype "passive"))
      (node (ref "T2") (pin "1") (pinfunction "D_1") (pintype "passive"))
      (node (ref "U10") (pin "6") (pinfunction "BAT_6") (pintype "bidirectional"))
    )
    (net (code "5") (name "BAT2") (class "Default")
      (node (ref "R27") (pin "2") (pinfunction "2_2") (pintype "passive"))
      (node (ref "SV2") (pin "7") (pinfunction "7_7") (pintype "passive"))
      (node (ref "T3") (pin "1") (pinfunction "D_1") (pintype "passive"))
      (node (ref "U12") (pin "6") (pinfunction "BAT_6") (pintype "bidirectional"))
    )
    (net (code "6") (name "BAT3") (class "Default")
      (node (ref "R29") (pin "2") (pinfunction "2_2") (pintype "passive"))
      (node (ref "SV2") (pin "1") (pinfunction "1_1") (pintype "passive"))
      (node (ref "T4") (pin "1") (pinfunction "D_1") (pintype "passive"))
      (node (ref "U13") (pin "6") (pinfunction "BAT_6") (pintype "bidirectional"))
    )
    (net (code "7") (name "BAT_ADC_0") (class "Default")
      (node (ref "C69") (pin "1") (pinfunction "1_1") (pintype "passive"))
      (node (ref "R31") (pin "1") (pinfunction "1_1") (pintype "passive"))
      (node (ref "R32") (pin "2") (pinfunction "2_2") (pintype "passive"))
      (node (ref "U2") (pin "4") (pinfunction "P0.02/AIN0_4") (pintype "bidirectional"))
    )
    (net (code "8") (name "BAT_ADC_1") (class "Default")
      (node (ref "C66") (pin "1") (pinfunction "1_1") (pintype "passive"))
      (node (ref "R25") (pin "1") (pinfunction "1_1") (pintype "passive"))
      (node (ref "R26") (pin "2") (pinfunction "2_2") (pintype "passive"))
      (node (ref "U2") (pin "5") (pinfunction "P0.03/AIN1_5") (pintype "bidirectional"))
    )
    (net (code "9") (name "BAT_ADC_2") (class "Default")
      (node (ref "C67") (pin "1") (pinfunction "1_1") (pintype "passive"))
      (node (ref "R27") (pin "1") (pinfunction "1_1") (pintype "passive"))
      (node (ref "R28") (pin "2") (pinfunction "2_2") (pintype "passive"))
      (node (ref "U2") (pin "6") (pinfunction "P0.04/AIN2_6") (pintype "bidirectional"))
    )
    (net (code "10") (name "BAT_ADC_3") (class "Default")
      (node (ref "C68") (pin "1") (pinfunction "1_1") (pintype "passive"))
      (node (ref "R29") (pin "1") (pinfunction "1_1") (pintype "passive"))
      (node (ref "R30") (pin "2") (pinfunction "2_2") (pintype "passive"))
      (node (ref "U2") (pin "7") (pinfunction "P0.05/AIN3_7") (pintype "bidirectional"))
    )
    (net (code "11") (name "BT_HALL") (class "Default")
      (node (ref "IC5") (pin "2") (pinfunction "OUT_2") (pintype "output"))
      (node (ref "U2") (pin "39") (pinfunction "P0.27_39") (pintype "bidirectional"))
    )
    (net (code "12") (name "BUZZER") (class "Default")
      (node (ref "R13") (pin "1") (pinfunction "1_1") (pintype "passive"))
      (node (ref "U2") (pin "11") (pinfunction "P0.09/NFC1_11") (pintype "bidirectional"))
    )
    (net (code "13") (name "CLOCK") (class "Default")
      (node (ref "U1") (pin "11") (pinfunction "SCK_11") (pintype "input"))
      (node (ref "U2") (pin "19") (pinfunction "P0.16_19") (pintype "bidirectional"))
    )
    (net (code "14") (name "CTRL0") (class "Default")
      (node (ref "U11") (pin "7") (pinfunction "CTRL_7") (pintype "bidirectional"))
    )
    (net (code "15") (name "CTRL1") (class "Default")
      (node (ref "U10") (pin "7") (pinfunction "CTRL_7") (pintype "bidirectional"))
    )
    (net (code "16") (name "CTRL2") (class "Default")
      (node (ref "U12") (pin "7") (pinfunction "CTRL_7") (pintype "bidirectional"))
    )
    (net (code "17") (name "CTRL3") (class "Default")
      (node (ref "U13") (pin "7") (pinfunction "CTRL_7") (pintype "bidirectional"))
    )
    (net (code "18") (name "DATA") (class "Default")
      (node (ref "U1") (pin "14") (pinfunction "SER_14") (pintype "input"))
      (node (ref "U2") (pin "18") (pinfunction "P0.15_18") (pintype "bidirectional"))
    )
    (net (code "19") (name "DEC1") (class "Default")
      (node (ref "C16") (pin "1") (pinfunction "1_1") (pintype "passive"))
      (node (ref "U2") (pin "1") (pinfunction "DEC1_1") (pintype "power_in"))
    )
    (net (code "20") (name "DEC2") (class "Default")
      (node (ref "C18") (pin "1") (pinfunction "1_1") (pintype "passive"))
      (node (ref "U2") (pin "32") (pinfunction "DEC2_32") (pintype "bidirectional"))
    )
    (net (code "21") (name "DEC3") (class "Default")
      (node (ref "C19") (pin "1") (pinfunction "1_1") (pintype "passive"))
      (node (ref "U2") (pin "33") (pinfunction "DEC3_33") (pintype "bidirectional"))
    )
    (net (code "22") (name "DEC4") (class "Default")
      (node (ref "C22") (pin "1") (pinfunction "1_1") (pintype "passive"))
      (node (ref "L4") (pin "2") (pinfunction "2_2") (pintype "passive"))
      (node (ref "U2") (pin "46") (pinfunction "DEC4_46") (pintype "power_in"))
    )
    (net (code "23") (name "DN") (class "Default")
      (node (ref "J2") (pin "A7") (pinfunction "DA-_A7") (pintype "passive"))
      (node (ref "J2") (pin "B7") (pinfunction "DB-_B7") (pintype "passive"))
      (node (ref "U5") (pin "4") (pinfunction "D-_4") (pintype "bidirectional"))
      (node (ref "U6") (pin "2") (pinfunction "A_2") (pintype "bidirectional"))
    )
    (net (code "24") (name "DP") (class "Default")
      (node (ref "J2") (pin "A6") (pinfunction "DA+_A6") (pintype "passive"))
      (node (ref "J2") (pin "B6") (pinfunction "DB+_B6") (pintype "passive"))
      (node (ref "U5") (pin "3") (pinfunction "D+_3") (pintype "bidirectional"))
      (node (ref "U6") (pin "3") (pinfunction "B_3") (pintype "bidirectional"))
    )
    (net (code "25") (name "EN_OUT") (class "Default")
      (node (ref "U1") (pin "13") (pinfunction "G_13") (pintype "input"))
      (node (ref "U2") (pin "22") (pinfunction "P0.19_22") (pintype "bidirectional"))
    )
    (net (code "26") (name "GND") (class "Default")
      (node (ref "C1") (pin "2") (pinfunction "2_2") (pintype "passive"))
      (node (ref "C10") (pin "2") (pinfunction "2_2") (pintype "passive"))
      (node (ref "C11") (pin "1") (pinfunction "1_1") (pintype "passive"))
      (node (ref "C12") (pin "1") (pinfunction "1_1") (pintype "passive"))
      (node (ref "C13") (pin "2") (pinfunction "2_2") (pintype "passive"))
      (node (ref "C14") (pin "2") (pinfunction "2_2") (pintype "passive"))
      (node (ref "C15") (pin "2") (pinfunction "2_2") (pintype "passive"))
      (node (ref "C16") (pin "2") (pinfunction "2_2") (pintype "passive"))
      (node (ref "C17") (pin "2") (pinfunction "2_2") (pintype "passive"))
      (node (ref "C18") (pin "2") (pinfunction "2_2") (pintype "passive"))
      (node (ref "C19") (pin "2") (pinfunction "2_2") (pintype "passive"))
      (node (ref "C2") (pin "2") (pinfunction "2_2") (pintype "passive"))
      (node (ref "C20") (pin "2") (pinfunction "2_2") (pintype "passive"))
      (node (ref "C21") (pin "2") (pinfunction "2_2") (pintype "passive"))
      (node (ref "C22") (pin "2") (pinfunction "2_2") (pintype "passive"))
      (node (ref "C23") (pin "1") (pinfunction "1_1") (pintype "passive"))
      (node (ref "C24") (pin "1") (pinfunction "1_1") (pintype "passive"))
      (node (ref "C25") (pin "2") (pinfunction "2_2") (pintype "passive"))
      (node (ref "C26") (pin "2") (pinfunction "2_2") (pintype "passive"))
      (node (ref "C27") (pin "2") (pinfunction "2_2") (pintype "passive"))
      (node (ref "C28") (pin "2") (pinfunction "2_2") (pintype "passive"))
      (node (ref "C29") (pin "2") (pinfunction "2_2") (pintype "passive"))
      (node (ref "C3") (pin "2") (pinfunction "2_2") (pintype "passive"))
      (node (ref "C30") (pin "2") (pinfunction "2_2") (pintype "passive"))
      (node (ref "C33") (pin "1") (pinfunction "1_1") (pintype "passive"))
      (node (ref "C34") (pin "2") (pinfunction "2_2") (pintype "passive"))
      (node (ref "C36") (pin "2") (pinfunction "2_2") (pintype "passive"))
      (node (ref "C37") (pin "2") (pinfunction "2_2") (pintype "passive"))
      (node (ref "C38") (pin "2") (pinfunction "2_2") (pintype "passive"))
      (node (ref "C39") (pin "1") (pinfunction "1_1") (pintype "passive"))
      (node (ref "C4") (pin "2") (pinfunction "2_2") (pintype "passive"))
      (node (ref "C40") (pin "2") (pinfunction "2_2") (pintype "passive"))
      (node (ref "C41") (pin "1") (pinfunction "1_1") (pintype "passive"))
      (node (ref "C42") (pin "2") (pinfunction "2_2") (pintype "passive"))
      (node (ref "C43") (pin "1") (pinfunction "1_1") (pintype "passive"))
      (node (ref "C44") (pin "1") (pinfunction "1_1") (pintype "passive"))
      (node (ref "C45") (pin "2") (pinfunction "2_2") (pintype "passive"))
      (node (ref "C46") (pin "1") (pinfunction "1_1") (pintype "passive"))
      (node (ref "C47") (pin "1") (pinfunction "1_1") (pintype "passive"))
      (node (ref "C48") (pin "2") (pinfunction "2_2") (pintype "passive"))
      (node (ref "C49") (pin "1") (pinfunction "1_1") (pintype "passive"))
      (node (ref "C5") (pin "1") (pinfunction "1_1") (pintype "passive"))
      (node (ref "C50") (pin "1") (pinfunction "1_1") (pintype "passive"))
      (node (ref "C51") (pin "2") (pinfunction "2_2") (pintype "passive"))
      (node (ref "C52") (pin "2") (pinfunction "2_2") (pintype "passive"))
      (node (ref "C53") (pin "2") (pinfunction "2_2") (pintype "passive"))
      (node (ref "C54") (pin "1") (pinfunction "1_1") (pintype "passive"))
      (node (ref "C57") (pin "1") (pinfunction "1_1") (pintype "passive"))
      (node (ref "C58") (pin "2") (pinfunction "2_2") (pintype "passive"))
      (node (ref "C59") (pin "1") (pinfunction "1_1") (pintype "passive"))
      (node (ref "C6") (pin "2") (pinfunction "2_2") (pintype "passive"))
      (node (ref "C62") (pin "1") (pinfunction "1_1") (pintype "passive"))
      (node (ref "C63") (pin "2") (pinfunction "2_2") (pintype "passive"))
      (node (ref "C64") (pin "1") (pinfunction "1_1") (pintype "passive"))
      (node (ref "C65") (pin "2") (pinfunction "2_2") (pintype "passive"))
      (node (ref "C66") (pin "2") (pinfunction "2_2") (pintype "passive"))
      (node (ref "C67") (pin "2") (pinfunction "2_2") (pintype "passive"))
      (node (ref "C68") (pin "2") (pinfunction "2_2") (pintype "passive"))
      (node (ref "C69") (pin "2") (pinfunction "2_2") (pintype "passive"))
      (node (ref "C7") (pin "2") (pinfunction "2_2") (pintype "passive"))
      (node (ref "C8") (pin "2") (pinfunction "2_2") (pintype "passive"))
      (node (ref "C9") (pin "1") (pinfunction "1_1") (pintype "passive"))
      (node (ref "IC1") (pin "3") (pinfunction "GND_3") (pintype "power_in"))
      (node (ref "IC2") (pin "3") (pinfunction "GND_3") (pintype "power_in"))
      (node (ref "IC3") (pin "3") (pinfunction "GND_3") (pintype "power_in"))
      (node (ref "IC4") (pin "3") (pinfunction "GND_3") (pintype "power_in"))
      (node (ref "IC5") (pin "3") (pinfunction "GND_3") (pintype "power_in"))
      (node (ref "J2") (pin "A1") (pinfunction "GND_A1_A1") (pintype "passive"))
      (node (ref "J2") (pin "A12") (pinfunction "GND_A12_A12") (pintype "passive"))
      (node (ref "J2") (pin "B1") (pinfunction "GND_B1_B1") (pintype "passive"))
      (node (ref "J2") (pin "B12") (pinfunction "GND_B12_B12") (pintype "passive"))
      (node (ref "J2") (pin "S1") (pinfunction "SHIELD_S1") (pintype "passive"))
      (node (ref "J2") (pin "S2") (pinfunction "SHIELD_S2") (pintype "passive"))
      (node (ref "J2") (pin "S3") (pinfunction "SHIELD_S3") (pintype "passive"))
      (node (ref "J2") (pin "S4") (pinfunction "SHIELD_S4") (pintype "passive"))
      (node (ref "JP1") (pin "1") (pinfunction "1_1") (pintype "passive"))
      (node (ref "L5") (pin "1") (pinfunction "1_1") (pintype "passive"))
      (node (ref "Q1") (pin "2") (pinfunction "E_2") (pintype "passive"))
      (node (ref "Q2") (pin "2") (pinfunction "S_2") (pintype "bidirectional"))
      (node (ref "R11") (pin "1") (pinfunction "1_1") (pintype "passive"))
      (node (ref "R12") (pin "1") (pinfunction "1_1") (pintype "passive"))
      (node (ref "R14") (pin "2") (pinfunction "2_2") (pintype "passive"))
      (node (ref "R15") (pin "2") (pinfunction "2_2") (pintype "passive"))
      (node (ref "R18") (pin "1") (pinfunction "1_1") (pintype "passive"))
      (node (ref "R21") (pin "1") (pinfunction "1_1") (pintype "passive"))
      (node (ref "R23") (pin "1") (pinfunction "1_1") (pintype "passive"))
      (node (ref "R26") (pin "1") (pinfunction "1_1") (pintype "passive"))
      (node (ref "R28") (pin "1") (pinfunction "1_1") (pintype "passive"))
      (node (ref "R3") (pin "2") (pinfunction "2_2") (pintype "passive"))
      (node (ref "R30") (pin "1") (pinfunction "1_1") (pintype "passive"))
      (node (ref "R32") (pin "1") (pinfunction "1_1") (pintype "passive"))
      (node (ref "R5") (pin "1") (pinfunction "1_1") (pintype "passive"))
      (node (ref "SV2") (pin "10") (pinfunction "10_10") (pintype "passive"))
      (node (ref "SV2") (pin "3") (pinfunction "3_3") (pintype "passive"))
      (node (ref "SV2") (pin "4") (pinfunction "4_4") (pintype "passive"))
      (node (ref "SV2") (pin "9") (pinfunction "9_9") (pintype "passive"))
      (node (ref "U$1") (pin "P$5") (pinfunction "GND_P$5") (pintype "power_in"))
      (node (ref "U1") (pin "8") (pinfunction "GND_8") (pintype "power_in"))
      (node (ref "U10") (pin "11") (pinfunction "EP_11") (pintype "bidirectional"))
      (node (ref "U10") (pin "3") (pinfunction "VSS_3") (pintype "bidirectional"))
      (node (ref "U11") (pin "11") (pinfunction "EP_11") (pintype "bidirectional"))
      (node (ref "U11") (pin "3") (pinfunction "VSS_3") (pintype "bidirectional"))
      (node (ref "U12") (pin "11") (pinfunction "EP_11") (pintype "bidirectional"))
      (node (ref "U12") (pin "3") (pinfunction "VSS_3") (pintype "bidirectional"))
      (node (ref "U13") (pin "11") (pinfunction "EP_11") (pintype "bidirectional"))
      (node (ref "U13") (pin "3") (pinfunction "VSS_3") (pintype "bidirectional"))
      (node (ref "U2") (pin "31") (pinfunction "VSS_31") (pintype "bidirectional"))
      (node (ref "U2") (pin "45") (pinfunction "VSS_45") (pintype "power_in"))
      (node (ref "U2") (pin "PAD") (pinfunction "VSS_PAD") (pintype "power_in"))
      (node (ref "U2") (pin "PAD@VIA01") (pinfunction "VSS_PAD@VIA01") (pintype "power_in"))
      (node (ref "U2") (pin "PAD@VIA02") (pinfunction "VSS_PAD@VIA02") (pintype "power_in"))
      (node (ref "U2") (pin "PAD@VIA03") (pinfunction "VSS_PAD@VIA03") (pintype "power_in"))
      (node (ref "U2") (pin "PAD@VIA04") (pinfunction "VSS_PAD@VIA04") (pintype "power_in"))
      (node (ref "U2") (pin "PAD@VIA05") (pinfunction "VSS_PAD@VIA05") (pintype "power_in"))
      (node (ref "U2") (pin "PAD@VIA06") (pinfunction "VSS_PAD@VIA06") (pintype "power_in"))
      (node (ref "U2") (pin "PAD@VIA07") (pinfunction "VSS_PAD@VIA07") (pintype "power_in"))
      (node (ref "U2") (pin "PAD@VIA08") (pinfunction "VSS_PAD@VIA08") (pintype "power_in"))
      (node (ref "U2") (pin "PAD@VIA09") (pinfunction "VSS_PAD@VIA09") (pintype "power_in"))
      (node (ref "U2") (pin "PAD@VIA10") (pinfunction "VSS_PAD@VIA10") (pintype "power_in"))
      (node (ref "U2") (pin "PAD@VIA11") (pinfunction "VSS_PAD@VIA11") (pintype "power_in"))
      (node (ref "U2") (pin "PAD@VIA12") (pinfunction "VSS_PAD@VIA12") (pintype "power_in"))
      (node (ref "U2") (pin "PAD@VIA13") (pinfunction "VSS_PAD@VIA13") (pintype "power_in"))
      (node (ref "U2") (pin "PAD@VIA14") (pinfunction "VSS_PAD@VIA14") (pintype "power_in"))
      (node (ref "U2") (pin "PAD@VIA15") (pinfunction "VSS_PAD@VIA15") (pintype "power_in"))
      (node (ref "U2") (pin "PAD@VIA16") (pinfunction "VSS_PAD@VIA16") (pintype "power_in"))
      (node (ref "U3") (pin "15") (pinfunction "PGND2_15") (pintype "power_in"))
      (node (ref "U3") (pin "21") (pinfunction "LGND_21") (pintype "power_in"))
      (node (ref "U3") (pin "25") (pinfunction "EPAD_25") (pintype "passive"))
      (node (ref "U3") (pin "4") (pinfunction "PGND1_4") (pintype "power_in"))
      (node (ref "U4") (pin "15") (pinfunction "PGND2_15") (pintype "power_in"))
      (node (ref "U4") (pin "21") (pinfunction "LGND_21") (pintype "power_in"))
      (node (ref "U4") (pin "25") (pinfunction "EPAD_25") (pintype "passive"))
      (node (ref "U4") (pin "4") (pinfunction "PGND1_4") (pintype "power_in"))
      (node (ref "U5") (pin "2") (pinfunction "GND_2") (pintype "power_in"))
      (node (ref "U5") (pin "25") (pinfunction "GND_25") (pintype "power_in"))
      (node (ref "U6") (pin "1") (pinfunction "GND_1") (pintype "bidirectional"))
      (node (ref "U7") (pin "15") (pinfunction "PGND2_15") (pintype "power_in"))
      (node (ref "U7") (pin "21") (pinfunction "LGND_21") (pintype "power_in"))
      (node (ref "U7") (pin "25") (pinfunction "EPAD_25") (pintype "passive"))
      (node (ref "U7") (pin "4") (pinfunction "PGND1_4") (pintype "power_in"))
      (node (ref "U8") (pin "11") (pinfunction "EXP_11") (pintype "passive"))
      (node (ref "U8") (pin "12") (pinfunction "GND_12") (pintype "power_in"))
      (node (ref "U8") (pin "13") (pinfunction "GND_13") (pintype "power_in"))
      (node (ref "U8") (pin "14") (pinfunction "GND_14") (pintype "power_in"))
      (node (ref "U8") (pin "15") (pinfunction "GND_15") (pintype "power_in"))
      (node (ref "U8") (pin "3") (pinfunction "PGND_3") (pintype "power_in"))
      (node (ref "U8") (pin "9") (pinfunction "GND_9") (pintype "power_in"))
      (node (ref "U9") (pin "1") (pinfunction "PGND_1") (pintype "passive"))
      (node (ref "U9") (pin "5") (pinfunction "AGND_5") (pintype "passive"))
      (node (ref "U9") (pin "EPAD") (pinfunction "EPAD_EPAD") (pintype "passive"))
      (node (ref "X3") (pin "2") (pinfunction "2_2") (pintype "passive"))
      (node (ref "X3") (pin "4") (pinfunction "4_4") (pintype "passive"))
    )
    (net (code "27") (name "III_HALL") (class "Default")
      (node (ref "IC4") (pin "2") (pinfunction "OUT_2") (pintype "output"))
      (node (ref "U2") (pin "40") (pinfunction "P0.28_40") (pintype "bidirectional"))
    )
    (net (code "28") (name "II_HALL") (class "Default")
      (node (ref "IC3") (pin "2") (pinfunction "OUT_2") (pintype "output"))
      (node (ref "U2") (pin "41") (pinfunction "P0.29_41") (pintype "bidirectional"))
    )
    (net (code "29") (name "IN1A") (class "Default")
      (node (ref "U1") (pin "15") (pinfunction "QA_15") (pintype "tri_state"))
      (node (ref "U3") (pin "23") (pinfunction "IN1A_23") (pintype "input"))
    )
    (net (code "30") (name "IN1B") (class "Default")
      (node (ref "U1") (pin "1") (pinfunction "QB_1") (pintype "tri_state"))
      (node (ref "U3") (pin "24") (pinfunction "IN1B_24") (pintype "input"))
    )
    (net (code "31") (name "IN2A") (class "Default")
      (node (ref "U1") (pin "2") (pinfunction "QC_2") (pintype "tri_state"))
      (node (ref "U3") (pin "20") (pinfunction "IN2A_20") (pintype "input"))
    )
    (net (code "32") (name "IN2B") (class "Default")
      (node (ref "U1") (pin "3") (pinfunction "QD_3") (pintype "tri_state"))
      (node (ref "U3") (pin "19") (pinfunction "IN2B_19") (pintype "input"))
    )
    (net (code "33") (name "IN3A") (class "Default")
      (node (ref "U1") (pin "4") (pinfunction "QE_4") (pintype "tri_state"))
      (node (ref "U7") (pin "23") (pinfunction "IN1A_23") (pintype "input"))
    )
    (net (code "34") (name "IN3B") (class "Default")
      (node (ref "U1") (pin "5") (pinfunction "QF_5") (pintype "tri_state"))
      (node (ref "U7") (pin "24") (pinfunction "IN1B_24") (pintype "input"))
    )
    (net (code "35") (name "IN4A") (class "Default")
      (node (ref "U1") (pin "6") (pinfunction "QG_6") (pintype "tri_state"))
      (node (ref "U7") (pin "20") (pinfunction "IN2A_20") (pintype "input"))
    )
    (net (code "36") (name "IN4B") (class "Default")
      (node (ref "U1") (pin "7") (pinfunction "QH_7") (pintype "tri_state"))
      (node (ref "U7") (pin "19") (pinfunction "IN2B_19") (pintype "input"))
    )
    (net (code "37") (name "IN5A") (class "Default")
      (node (ref "U2") (pin "38") (pinfunction "P0.26_38") (pintype "bidirectional"))
      (node (ref "U4") (pin "23") (pinfunction "IN1A_23") (pintype "input"))
    )
    (net (code "38") (name "IN5B") (class "Default")
      (node (ref "U2") (pin "37") (pinfunction "P0.25_37") (pintype "bidirectional"))
      (node (ref "U4") (pin "24") (pinfunction "IN1B_24") (pintype "input"))
    )
    (net (code "39") (name "ISENSE0") (class "Default")
      (node (ref "R5") (pin "2") (pinfunction "2_2") (pintype "passive"))
      (node (ref "U11") (pin "2") (pinfunction "IMON_2") (pintype "bidirectional"))
    )
    (net (code "40") (name "ISENSE1") (class "Default")
      (node (ref "R18") (pin "2") (pinfunction "2_2") (pintype "passive"))
      (node (ref "U10") (pin "2") (pinfunction "IMON_2") (pintype "bidirectional"))
    )
    (net (code "41") (name "ISENSE2") (class "Default")
      (node (ref "R21") (pin "2") (pinfunction "2_2") (pintype "passive"))
      (node (ref "U12") (pin "2") (pinfunction "IMON_2") (pintype "bidirectional"))
    )
    (net (code "42") (name "ISENSE3") (class "Default")
      (node (ref "R23") (pin "2") (pinfunction "2_2") (pintype "passive"))
      (node (ref "U13") (pin "2") (pinfunction "IMON_2") (pintype "bidirectional"))
    )
    (net (code "43") (name "I_HALL") (class "Default")
      (node (ref "IC2") (pin "2") (pinfunction "OUT_2") (pintype "output"))
      (node (ref "U2") (pin "42") (pinfunction "P0.30_42") (pintype "bidirectional"))
    )
    (net (code "44") (name "LED_B") (class "Default")
      (node (ref "R10") (pin "2") (pinfunction "2_2") (pintype "passive"))
      (node (ref "TP29") (pin "TP") (pinfunction "TP_TP") (pintype "input"))
      (node (ref "U2") (pin "8") (pinfunction "P0.06_8") (pintype "bidirectional"))
    )
    (net (code "45") (name "LED_G") (class "Default")
      (node (ref "R2") (pin "2") (pinfunction "2_2") (pintype "passive"))
      (node (ref "TP31") (pin "TP") (pinfunction "TP_TP") (pintype "input"))
      (node (ref "U2") (pin "10") (pinfunction "P0.08_10") (pintype "bidirectional"))
    )
    (net (code "46") (name "LED_R") (class "Default")
      (node (ref "R4") (pin "2") (pinfunction "2_2") (pintype "passive"))
      (node (ref "TP30") (pin "TP") (pinfunction "TP_TP") (pintype "input"))
      (node (ref "U10") (pin "8") (pinfunction "~{CHG}_8") (pintype "bidirectional"))
      (node (ref "U11") (pin "8") (pinfunction "~{CHG}_8") (pintype "bidirectional"))
      (node (ref "U12") (pin "8") (pinfunction "~{CHG}_8") (pintype "bidirectional"))
      (node (ref "U13") (pin "8") (pinfunction "~{CHG}_8") (pintype "bidirectional"))
      (node (ref "U2") (pin "9") (pinfunction "P0.07_9") (pintype "bidirectional"))
    )
    (net (code "47") (name "Net-(C28-Pad1)") (class "Default")
      (node (ref "C28") (pin "1") (pinfunction "1_1") (pintype "passive"))
      (node (ref "R7") (pin "1") (pinfunction "1_1") (pintype "passive"))
    )
    (net (code "48") (name "Net-(C35-Pad1)") (class "Default")
      (node (ref "C35") (pin "1") (pinfunction "1_1") (pintype "passive"))
      (node (ref "L5") (pin "2") (pinfunction "2_2") (pintype "passive"))
      (node (ref "L6") (pin "2") (pinfunction "2_2") (pintype "passive"))
    )
    (net (code "49") (name "Net-(C35-Pad2)") (class "Default")
      (node (ref "C35") (pin "2") (pinfunction "2_2") (pintype "passive"))
      (node (ref "L2") (pin "2") (pinfunction "2_2") (pintype "passive"))
    )
    (net (code "50") (name "Net-(D1-B_C)") (class "Default")
      (node (ref "D1") (pin "5") (pinfunction "B_C_5") (pintype "passive"))
      (node (ref "R10") (pin "1") (pinfunction "1_1") (pintype "passive"))
    )
    (net (code "51") (name "Net-(D1-G_C)") (class "Default")
      (node (ref "D1") (pin "1") (pinfunction "G_C_1") (pintype "passive"))
      (node (ref "R2") (pin "1") (pinfunction "1_1") (pintype "passive"))
    )
    (net (code "52") (name "Net-(D1-R_C)") (class "Default")
      (node (ref "D1") (pin "3") (pinfunction "R_C_3") (pintype "passive"))
      (node (ref "R4") (pin "1") (pinfunction "1_1") (pintype "passive"))
    )
    (net (code "53") (name "Net-(J2-CC1)") (class "Default")
      (node (ref "J2") (pin "A5") (pinfunction "CC1_A5") (pintype "passive"))
      (node (ref "R11") (pin "2") (pinfunction "2_2") (pintype "passive"))
    )
    (net (code "54") (name "Net-(J2-CC2)") (class "Default")
      (node (ref "J2") (pin "B5") (pinfunction "CC2_B5") (pintype "passive"))
      (node (ref "R14") (pin "1") (pinfunction "1_1") (pintype "passive"))
    )
    (net (code "55") (name "Net-(L1-1)") (class "Default")
      (node (ref "L1") (pin "P$1") (pinfunction "1_P$1") (pintype "passive"))
      (node (ref "U8") (pin "2") (pinfunction "L2_2") (pintype "input"))
    )
    (net (code "56") (name "Net-(L1-2)") (class "Default")
      (node (ref "L1") (pin "P$2") (pinfunction "2_P$2") (pintype "passive"))
      (node (ref "U8") (pin "4") (pinfunction "L1_4") (pintype "input"))
    )
    (net (code "57") (name "Net-(L3-Pad2)") (class "Default")
      (node (ref "L3") (pin "2") (pinfunction "2_2") (pintype "passive"))
      (node (ref "L4") (pin "1") (pinfunction "1_1") (pintype "passive"))
    )
    (net (code "58") (name "Net-(L6-Pad1)") (class "Default")
      (node (ref "L6") (pin "1") (pinfunction "1_1") (pintype "passive"))
      (node (ref "U$16") (pin "P$1") (pinfunction "P$1_P$1") (pintype "bidirectional"))
    )
    (net (code "59") (name "Net-(L7-2)") (class "Default")
      (node (ref "D2") (pin "A") (pinfunction "A_A") (pintype "passive"))
      (node (ref "L7") (pin "P$2") (pinfunction "2_P$2") (pintype "passive"))
      (node (ref "U9") (pin "8") (pinfunction "SW_8") (pintype "passive"))
    )
    (net (code "60") (name "Net-(Q1-B)") (class "Default")
      (node (ref "Q1") (pin "1") (pinfunction "B_1") (pintype "passive"))
      (node (ref "R13") (pin "2") (pinfunction "2_2") (pintype "passive"))
      (node (ref "R15") (pin "1") (pinfunction "1_1") (pintype "passive"))
    )
    (net (code "61") (name "Net-(Q1-C)") (class "Default")
      (node (ref "LS1") (pin "1") (pinfunction "1_1") (pintype "passive"))
      (node (ref "Q1") (pin "3") (pinfunction "C_3") (pintype "passive"))
      (node (ref "R6") (pin "2") (pinfunction "2_2") (pintype "passive"))
    )
    (net (code "62") (name "Net-(Q2-D)") (class "Default")
      (node (ref "D3") (pin "A") (pinfunction "A_A") (pintype "passive"))
      (node (ref "Q2") (pin "3") (pinfunction "D_3") (pintype "bidirectional"))
      (node (ref "X2") (pin "1") (pinfunction "KL_1") (pintype "passive"))
    )
    (net (code "63") (name "Net-(T1-G)") (class "Default")
      (node (ref "R17") (pin "1") (pinfunction "1_1") (pintype "passive"))
      (node (ref "T1") (pin "3") (pinfunction "G_3") (pintype "passive"))
    )
    (net (code "64") (name "Net-(T1-S)") (class "Default")
      (node (ref "C39") (pin "2") (pinfunction "2_2") (pintype "passive"))
      (node (ref "D5") (pin "A") (pinfunction "A_A") (pintype "passive"))
      (node (ref "T1") (pin "2") (pinfunction "S_2") (pintype "passive"))
      (node (ref "U11") (pin "10") (pinfunction "OUT_10") (pintype "bidirectional"))
    )
    (net (code "65") (name "Net-(T2-G)") (class "Default")
      (node (ref "R20") (pin "1") (pinfunction "1_1") (pintype "passive"))
      (node (ref "T2") (pin "3") (pinfunction "G_3") (pintype "passive"))
    )
    (net (code "66") (name "Net-(T2-S)") (class "Default")
      (node (ref "C43") (pin "2") (pinfunction "2_2") (pintype "passive"))
      (node (ref "D4") (pin "A") (pinfunction "A_A") (pintype "passive"))
      (node (ref "T2") (pin "2") (pinfunction "S_2") (pintype "passive"))
      (node (ref "U10") (pin "10") (pinfunction "OUT_10") (pintype "bidirectional"))
    )
    (net (code "67") (name "Net-(T3-G)") (class "Default")
      (node (ref "R22") (pin "1") (pinfunction "1_1") (pintype "passive"))
      (node (ref "T3") (pin "3") (pinfunction "G_3") (pintype "passive"))
    )
    (net (code "68") (name "Net-(T3-S)") (class "Default")
      (node (ref "C46") (pin "2") (pinfunction "2_2") (pintype "passive"))
      (node (ref "D6") (pin "A") (pinfunction "A_A") (pintype "passive"))
      (node (ref "T3") (pin "2") (pinfunction "S_2") (pintype "passive"))
      (node (ref "U12") (pin "10") (pinfunction "OUT_10") (pintype "bidirectional"))
    )
    (net (code "69") (name "Net-(T4-G)") (class "Default")
      (node (ref "R24") (pin "1") (pinfunction "1_1") (pintype "passive"))
      (node (ref "T4") (pin "3") (pinfunction "G_3") (pintype "passive"))
    )
    (net (code "70") (name "Net-(T4-S)") (class "Default")
      (node (ref "C49") (pin "2") (pinfunction "2_2") (pintype "passive"))
      (node (ref "D7") (pin "A") (pinfunction "A_A") (pintype "passive"))
      (node (ref "T4") (pin "2") (pinfunction "S_2") (pintype "passive"))
      (node (ref "U13") (pin "10") (pinfunction "OUT_10") (pintype "bidirectional"))
    )
    (net (code "71") (name "Net-(U1-SCL)") (class "Default")
      (node (ref "R1") (pin "1") (pinfunction "1_1") (pintype "passive"))
      (node (ref "U1") (pin "10") (pinfunction "SCL_10") (pintype "input"))
    )
    (net (code "72") (name "Net-(U2-ANT)") (class "Default")
      (node (ref "C15") (pin "1") (pinfunction "1_1") (pintype "passive"))
      (node (ref "L2") (pin "1") (pinfunction "1_1") (pintype "passive"))
      (node (ref "U2") (pin "30") (pinfunction "ANT_30") (pintype "bidirectional"))
    )
    (net (code "73") (name "Net-(U2-DCC)") (class "Default")
      (node (ref "L3") (pin "1") (pinfunction "1_1") (pintype "passive"))
      (node (ref "U2") (pin "47") (pinfunction "DCC_47") (pintype "output"))
    )
    (net (code "74") (name "Net-(U2-XC1)") (class "Default")
      (node (ref "C14") (pin "1") (pinfunction "1_1") (pintype "passive"))
      (node (ref "U2") (pin "34") (pinfunction "XC1_34") (pintype "input"))
      (node (ref "X3") (pin "1") (pinfunction "1_1") (pintype "passive"))
    )
    (net (code "75") (name "Net-(U2-XC2)") (class "Default")
      (node (ref "C13") (pin "1") (pinfunction "1_1") (pintype "passive"))
      (node (ref "U2") (pin "35") (pinfunction "XC2_35") (pintype "output"))
      (node (ref "X3") (pin "3") (pinfunction "3_3") (pintype "passive"))
    )
    (net (code "76") (name "Net-(U3-C1H)") (class "Default")
      (node (ref "C31") (pin "2") (pinfunction "2_2") (pintype "passive"))
      (node (ref "U3") (pin "11") (pinfunction "C1H_11") (pintype "passive"))
    )
    (net (code "77") (name "Net-(U3-C1L)") (class "Default")
      (node (ref "C31") (pin "1") (pinfunction "1_1") (pintype "passive"))
      (node (ref "U3") (pin "12") (pinfunction "C1L_12") (pintype "passive"))
    )
    (net (code "78") (name "Net-(U3-C2H)") (class "Default")
      (node (ref "C32") (pin "1") (pinfunction "1_1") (pintype "passive"))
      (node (ref "U3") (pin "10") (pinfunction "C2H_10") (pintype "passive"))
    )
    (net (code "79") (name "Net-(U3-C2L)") (class "Default")
      (node (ref "C32") (pin "2") (pinfunction "2_2") (pintype "passive"))
      (node (ref "U3") (pin "13") (pinfunction "C2L_13") (pintype "passive"))
    )
    (net (code "80") (name "Net-(U3-CRES)") (class "Default")
      (node (ref "C33") (pin "2") (pinfunction "2_2") (pintype "passive"))
      (node (ref "U3") (pin "9") (pinfunction "CRES_9") (pintype "power_in"))
    )
    (net (code "81") (name "Net-(U4-C1H)") (class "Default")
      (node (ref "C55") (pin "2") (pinfunction "2_2") (pintype "passive"))
      (node (ref "U4") (pin "11") (pinfunction "C1H_11") (pintype "passive"))
    )
    (net (code "82") (name "Net-(U4-C1L)") (class "Default")
      (node (ref "C55") (pin "1") (pinfunction "1_1") (pintype "passive"))
      (node (ref "U4") (pin "12") (pinfunction "C1L_12") (pintype "passive"))
    )
    (net (code "83") (name "Net-(U4-C2H)") (class "Default")
      (node (ref "C56") (pin "1") (pinfunction "1_1") (pintype "passive"))
      (node (ref "U4") (pin "10") (pinfunction "C2H_10") (pintype "passive"))
    )
    (net (code "84") (name "Net-(U4-C2L)") (class "Default")
      (node (ref "C56") (pin "2") (pinfunction "2_2") (pintype "passive"))
      (node (ref "U4") (pin "13") (pinfunction "C2L_13") (pintype "passive"))
    )
    (net (code "85") (name "Net-(U4-CRES)") (class "Default")
      (node (ref "C57") (pin "2") (pinfunction "2_2") (pintype "passive"))
      (node (ref "U4") (pin "9") (pinfunction "CRES_9") (pintype "power_in"))
    )
    (net (code "86") (name "Net-(U5-SUSPEND)") (class "Default")
      (node (ref "R8") (pin "1") (pinfunction "1_1") (pintype "passive"))
      (node (ref "TP28") (pin "TP") (pinfunction "TP_TP") (pintype "input"))
      (node (ref "U5") (pin "17") (pinfunction "SUSPEND_17") (pintype "output"))
    )
    (net (code "87") (name "Net-(U7-C1H)") (class "Default")
      (node (ref "C60") (pin "2") (pinfunction "2_2") (pintype "passive"))
      (node (ref "U7") (pin "11") (pinfunction "C1H_11") (pintype "passive"))
    )
    (net (code "88") (name "Net-(U7-C1L)") (class "Default")
      (node (ref "C60") (pin "1") (pinfunction "1_1") (pintype "passive"))
      (node (ref "U7") (pin "12") (pinfunction "C1L_12") (pintype "passive"))
    )
    (net (code "89") (name "Net-(U7-C2H)") (class "Default")
      (node (ref "C61") (pin "1") (pinfunction "1_1") (pintype "passive"))
      (node (ref "U7") (pin "10") (pinfunction "C2H_10") (pintype "passive"))
    )
    (net (code "90") (name "Net-(U7-C2L)") (class "Default")
      (node (ref "C61") (pin "2") (pinfunction "2_2") (pintype "passive"))
      (node (ref "U7") (pin "13") (pinfunction "C2L_13") (pintype "passive"))
    )
    (net (code "91") (name "Net-(U7-CRES)") (class "Default")
      (node (ref "C62") (pin "2") (pinfunction "2_2") (pintype "passive"))
      (node (ref "U7") (pin "9") (pinfunction "CRES_9") (pintype "power_in"))
    )
    (net (code "92") (name "Net-(U8-EN)") (class "Default")
      (node (ref "C9") (pin "2") (pinfunction "2_2") (pintype "passive"))
      (node (ref "JP1") (pin "3") (pinfunction "3_3") (pintype "passive"))
      (node (ref "U8") (pin "6") (pinfunction "EN_6") (pintype "input"))
      (node (ref "U8") (pin "8") (pinfunction "VINA_8") (pintype "input"))
    )
    (net (code "93") (name "Net-(U8-PS{slash}SYNC)") (class "Default")
      (node (ref "JP1") (pin "2") (pinfunction "2_2") (pintype "passive"))
      (node (ref "U8") (pin "7") (pinfunction "PS/SYNC_7") (pintype "input"))
    )
    (net (code "94") (name "Net-(U9-COMP)") (class "Default")
      (node (ref "C29") (pin "1") (pinfunction "1_1") (pintype "passive"))
      (node (ref "R7") (pin "2") (pinfunction "2_2") (pintype "passive"))
      (node (ref "U9") (pin "4") (pinfunction "COMP_4") (pintype "passive"))
    )
    (net (code "95") (name "Net-(U9-FB)") (class "Default")
      (node (ref "R12") (pin "2") (pinfunction "2_2") (pintype "passive"))
      (node (ref "R9") (pin "1") (pinfunction "1_1") (pintype "passive"))
      (node (ref "U9") (pin "6") (pinfunction "FB_6") (pintype "passive"))
    )
    (net (code "96") (name "Net-(U9-SS)") (class "Default")
      (node (ref "C52") (pin "1") (pinfunction "1_1") (pintype "passive"))
      (node (ref "U9") (pin "7") (pinfunction "SS_7") (pintype "passive"))
    )
    (net (code "97") (name "Net-(U10-BGATE)") (class "Default")
      (node (ref "R20") (pin "2") (pinfunction "2_2") (pintype "passive"))
      (node (ref "U10") (pin "9") (pinfunction "BGATE_9") (pintype "bidirectional"))
    )
    (net (code "98") (name "Net-(U10-LDO)") (class "Default")
      (node (ref "C44") (pin "2") (pinfunction "2_2") (pintype "passive"))
      (node (ref "U10") (pin "4") (pinfunction "LDO_4") (pintype "bidirectional"))
    )
    (net (code "99") (name "Net-(U11-BGATE)") (class "Default")
      (node (ref "R17") (pin "2") (pinfunction "2_2") (pintype "passive"))
      (node (ref "U11") (pin "9") (pinfunction "BGATE_9") (pintype "bidirectional"))
    )
    (net (code "100") (name "Net-(U11-LDO)") (class "Default")
      (node (ref "C41") (pin "2") (pinfunction "2_2") (pintype "passive"))
      (node (ref "U11") (pin "4") (pinfunction "LDO_4") (pintype "bidirectional"))
    )
    (net (code "101") (name "Net-(U12-BGATE)") (class "Default")
      (node (ref "R22") (pin "2") (pinfunction "2_2") (pintype "passive"))
      (node (ref "U12") (pin "9") (pinfunction "BGATE_9") (pintype "bidirectional"))
    )
    (net (code "102") (name "Net-(U12-LDO)") (class "Default")
      (node (ref "C47") (pin "2") (pinfunction "2_2") (pintype "passive"))
      (node (ref "U12") (pin "4") (pinfunction "LDO_4") (pintype "bidirectional"))
    )
    (net (code "103") (name "Net-(U13-BGATE)") (class "Default")
      (node (ref "R24") (pin "2") (pinfunction "2_2") (pintype "passive"))
      (node (ref "U13") (pin "9") (pinfunction "BGATE_9") (pintype "bidirectional"))
    )
    (net (code "104") (name "Net-(U13-LDO)") (class "Default")
      (node (ref "C50") (pin "2") (pinfunction "2_2") (pintype "passive"))
      (node (ref "U13") (pin "4") (pinfunction "LDO_4") (pintype "bidirectional"))
    )
    (net (code "105") (name "ON_HALL") (class "Default")
      (node (ref "IC1") (pin "2") (pinfunction "OUT_2") (pintype "output"))
      (node (ref "U2") (pin "43") (pinfunction "P0.31_43") (pintype "bidirectional"))
    )
    (net (code "106") (name "OUT1A") (class "Default")
      (node (ref "J1") (pin "1") (pinfunction "1_1") (pintype "bidirectional"))
      (node (ref "U3") (pin "5") (pinfunction "OUT1A_5") (pintype "output"))
    )
    (net (code "107") (name "OUT1B") (class "Default")
      (node (ref "J1") (pin "2") (pinfunction "2_2") (pintype "bidirectional"))
      (node (ref "U3") (pin "14") (pinfunction "OUT1B_14") (pintype "output"))
    )
    (net (code "108") (name "OUT2A") (class "Default")
      (node (ref "J3") (pin "1") (pinfunction "1_1") (pintype "bidirectional"))
      (node (ref "U3") (pin "3") (pinfunction "OUT2A_3") (pintype "output"))
    )
    (net (code "109") (name "OUT2B") (class "Default")
      (node (ref "J3") (pin "2") (pinfunction "2_2") (pintype "bidirectional"))
      (node (ref "U3") (pin "16") (pinfunction "OUT2B_16") (pintype "output"))
    )
    (net (code "110") (name "OUT3A") (class "Default")
      (node (ref "J4") (pin "1") (pinfunction "1_1") (pintype "bidirectional"))
      (node (ref "U7") (pin "5") (pinfunction "OUT1A_5") (pintype "output"))
    )
    (net (code "111") (name "OUT3B") (class "Default")
      (node (ref "J4") (pin "2") (pinfunction "2_2") (pintype "bidirectional"))
      (node (ref "U7") (pin "14") (pinfunction "OUT1B_14") (pintype "output"))
    )
    (net (code "112") (name "OUT4A") (class "Default")
      (node (ref "J5") (pin "1") (pinfunction "1_1") (pintype "bidirectional"))
      (node (ref "U7") (pin "3") (pinfunction "OUT2A_3") (pintype "output"))
    )
    (net (code "113") (name "OUT4B") (class "Default")
      (node (ref "J5") (pin "2") (pinfunction "2_2") (pintype "bidirectional"))
      (node (ref "U7") (pin "16") (pinfunction "OUT2B_16") (pintype "output"))
    )
    (net (code "114") (name "OUT5A") (class "Default")
      (node (ref "J6") (pin "1") (pinfunction "1_1") (pintype "bidirectional"))
      (node (ref "U4") (pin "5") (pinfunction "OUT1A_5") (pintype "output"))
    )
    (net (code "115") (name "OUT5B") (class "Default")
      (node (ref "J6") (pin "2") (pinfunction "2_2") (pintype "bidirectional"))
      (node (ref "U4") (pin "14") (pinfunction "OUT1B_14") (pintype "output"))
    )
    (net (code "116") (name "P0.00{slash}XL1") (class "Default")
      (node (ref "C23") (pin "2") (pinfunction "2_2") (pintype "passive"))
      (node (ref "U2") (pin "2") (pinfunction "P0.00/XL1_2") (pintype "bidirectional"))
      (node (ref "X4") (pin "1") (pinfunction "1_1") (pintype "passive"))
    )
    (net (code "117") (name "P0.01{slash}XL2") (class "Default")
      (node (ref "C24") (pin "2") (pinfunction "2_2") (pintype "passive"))
      (node (ref "U2") (pin "3") (pinfunction "P0.01/XL2_3") (pintype "bidirectional"))
      (node (ref "X4") (pin "2") (pinfunction "2_2") (pintype "passive"))
    )
    (net (code "118") (name "P0.22") (class "Default")
      (node (ref "C38") (pin "1") (pinfunction "1_1") (pintype "passive"))
      (node (ref "R19") (pin "1") (pinfunction "1_1") (pintype "passive"))
      (node (ref "U2") (pin "27") (pinfunction "P0.22_27") (pintype "bidirectional"))
    )
    (net (code "119") (name "P0.24") (class "Default")
      (node (ref "R19") (pin "2") (pinfunction "2_2") (pintype "passive"))
      (node (ref "U2") (pin "29") (pinfunction "P0.24_29") (pintype "bidirectional"))
    )
    (net (code "120") (name "PSAVE") (class "Default")
      (node (ref "U2") (pin "23") (pinfunction "P0.20_23") (pintype "bidirectional"))
      (node (ref "U3") (pin "2") (pinfunction "~{PSAVE}_2") (pintype "input"))
      (node (ref "U4") (pin "2") (pinfunction "~{PSAVE}_2") (pintype "input"))
      (node (ref "U7") (pin "2") (pinfunction "~{PSAVE}_2") (pintype "input"))
    )
    (net (code "121") (name "PUMP") (class "Default")
      (node (ref "Q2") (pin "1") (pinfunction "G_1") (pintype "bidirectional"))
      (node (ref "R3") (pin "1") (pinfunction "1_1") (pintype "passive"))
    )
    (net (code "122") (name "PWR_EN_1") (class "Default")
      (node (ref "U2") (pin "12") (pinfunction "P0.10/NFC2_12") (pintype "bidirectional"))
      (node (ref "U9") (pin "3") (pinfunction "EN_3") (pintype "passive"))
    )
    (net (code "123") (name "RCK") (class "Default")
      (node (ref "U1") (pin "12") (pinfunction "RCK_12") (pintype "input"))
      (node (ref "U2") (pin "20") (pinfunction "P0.17_20") (pintype "bidirectional"))
    )
    (net (code "124") (name "RST_CP") (class "Default")
      (node (ref "R16") (pin "2") (pinfunction "2_2") (pintype "passive"))
      (node (ref "TP27") (pin "TP") (pinfunction "TP_TP") (pintype "input"))
      (node (ref "U2") (pin "14") (pinfunction "P0.11_14") (pintype "bidirectional"))
      (node (ref "U5") (pin "9") (pinfunction "~{RST}_9") (pintype "bidirectional"))
    )
    (net (code "125") (name "RST_NRF") (class "Default")
      (node (ref "U$1") (pin "P$3") (pinfunction "NRESET_P$3") (pintype "bidirectional"))
      (node (ref "U2") (pin "24") (pinfunction "P0.21/RESET_24") (pintype "bidirectional"))
    )
    (net (code "126") (name "RXD") (class "Default")
      (node (ref "TP22") (pin "TP") (pinfunction "TP_TP") (pintype "input"))
      (node (ref "U2") (pin "17") (pinfunction "P0.14_17") (pintype "bidirectional"))
      (node (ref "U5") (pin "20") (pinfunction "RXD_20") (pintype "input"))
    )
    (net (code "127") (name "SUSPEND") (class "Default")
      (node (ref "R8") (pin "2") (pinfunction "2_2") (pintype "passive"))
      (node (ref "U2") (pin "15") (pinfunction "P0.12_15") (pintype "bidirectional"))
    )
    (net (code "128") (name "SWCLK") (class "Default")
      (node (ref "U$1") (pin "P$4") (pinfunction "SWCLK_P$4") (pintype "bidirectional"))
      (node (ref "U2") (pin "25") (pinfunction "SWDCLK_25") (pintype "input"))
    )
    (net (code "129") (name "SWDIO") (class "Default")
      (node (ref "U$1") (pin "P$2") (pinfunction "SWDIO_P$2") (pintype "bidirectional"))
      (node (ref "U2") (pin "26") (pinfunction "SWDIO_26") (pintype "bidirectional"))
    )
    (net (code "130") (name "SWO") (class "Default")
      (node (ref "U$1") (pin "P$6") (pinfunction "SWO_P$6") (pintype "bidirectional"))
      (node (ref "U2") (pin "21") (pinfunction "P0.18/SWO_21") (pintype "bidirectional"))
    )
    (net (code "131") (name "TS0") (class "Default")
      (node (ref "SV2") (pin "8") (pinfunction "8_8") (pintype "passive"))
      (node (ref "U11") (pin "5") (pinfunction "TS_5") (pintype "bidirectional"))
    )
    (net (code "132") (name "TS1") (class "Default")
      (node (ref "SV2") (pin "2") (pinfunction "2_2") (pintype "passive"))
      (node (ref "U10") (pin "5") (pinfunction "TS_5") (pintype "bidirectional"))
    )
    (net (code "133") (name "TS2") (class "Default")
      (node (ref "SV2") (pin "11") (pinfunction "11_11") (pintype "passive"))
      (node (ref "U12") (pin "5") (pinfunction "TS_5") (pintype "bidirectional"))
    )
    (net (code "134") (name "TS3") (class "Default")
      (node (ref "SV2") (pin "5") (pinfunction "5_5") (pintype "passive"))
      (node (ref "U13") (pin "5") (pinfunction "TS_5") (pintype "bidirectional"))
    )
    (net (code "135") (name "TXD") (class "Default")
      (node (ref "TP21") (pin "TP") (pinfunction "TP_TP") (pintype "input"))
      (node (ref "U2") (pin "16") (pinfunction "P0.13_16") (pintype "bidirectional"))
      (node (ref "U5") (pin "21") (pinfunction "TXD_21") (pintype "output"))
    )
    (net (code "136") (name "VBUS") (class "Default")
      (node (ref "C12") (pin "2") (pinfunction "2_2") (pintype "passive"))
      (node (ref "C27") (pin "1") (pinfunction "1_1") (pintype "passive"))
      (node (ref "C34") (pin "1") (pinfunction "1_1") (pintype "passive"))
      (node (ref "C42") (pin "1") (pinfunction "1_1") (pintype "passive"))
      (node (ref "C45") (pin "1") (pinfunction "1_1") (pintype "passive"))
      (node (ref "C48") (pin "1") (pinfunction "1_1") (pintype "passive"))
      (node (ref "J2") (pin "B3") (pinfunction "TX2-_B3") (pintype "passive"))
      (node (ref "TP11") (pin "TP") (pinfunction "TP_TP") (pintype "input"))
      (node (ref "U10") (pin "1") (pinfunction "IN_1") (pintype "bidirectional"))
      (node (ref "U11") (pin "1") (pinfunction "IN_1") (pintype "bidirectional"))
      (node (ref "U12") (pin "1") (pinfunction "IN_1") (pintype "bidirectional"))
      (node (ref "U13") (pin "1") (pinfunction "IN_1") (pintype "bidirectional"))
      (node (ref "U5") (pin "7") (pinfunction "VREGIN_7") (pintype "input"))
      (node (ref "U5") (pin "8") (pinfunction "VBUS_8") (pintype "input"))
      (node (ref "U6") (pin "4") (pinfunction "C_4") (pintype "bidirectional"))
    )
    (net (code "137") (name "VCC") (class "Default")
      (node (ref "C25") (pin "1") (pinfunction "1_1") (pintype "passive"))
      (node (ref "C26") (pin "1") (pinfunction "1_1") (pintype "passive"))
      (node (ref "C30") (pin "1") (pinfunction "1_1") (pintype "passive"))
      (node (ref "C36") (pin "1") (pinfunction "1_1") (pintype "passive"))
      (node (ref "C37") (pin "1") (pinfunction "1_1") (pintype "passive"))
      (node (ref "C51") (pin "1") (pinfunction "1_1") (pintype "passive"))
      (node (ref "D4") (pin "C") (pinfunction "C_C") (pintype "passive"))
      (node (ref "D5") (pin "C") (pinfunction "C_C") (pintype "passive"))
      (node (ref "D6") (pin "C") (pinfunction "C_C") (pintype "passive"))
      (node (ref "D7") (pin "C") (pinfunction "C_C") (pintype "passive"))
      (node (ref "L7") (pin "P$1") (pinfunction "1_P$1") (pintype "passive"))
      (node (ref "U8") (pin "5") (pinfunction "VIN_5") (pintype "input"))
      (node (ref "U9") (pin "2") (pinfunction "VIN_2") (pintype "passive"))
    )
    (net (code "138") (name "VDD") (class "Default")
      (node (ref "C5") (pin "2") (pinfunction "2_2") (pintype "passive"))
      (node (ref "C6") (pin "1") (pinfunction "1_1") (pintype "passive"))
      (node (ref "R16") (pin "1") (pinfunction "1_1") (pintype "passive"))
      (node (ref "U5") (pin "5") (pinfunction "VIO_5") (pintype "power_in"))
      (node (ref "U5") (pin "6") (pinfunction "VDD_6") (pintype "power_in"))
    )
    (net (code "139") (name "unconnected-(J2-RX1+-PadB11)") (class "Default")
      (node (ref "J2") (pin "B11") (pinfunction "RX1+_B11") (pintype "passive"))
    )
    (net (code "140") (name "unconnected-(J2-RX1--PadB10)") (class "Default")
      (node (ref "J2") (pin "B10") (pinfunction "RX1-_B10") (pintype "passive"))
    )
    (net (code "141") (name "unconnected-(J2-RX2+-PadA11)") (class "Default")
      (node (ref "J2") (pin "A11") (pinfunction "RX2+_A11") (pintype "passive"))
    )
    (net (code "142") (name "unconnected-(J2-RX2--PadA10)") (class "Default")
      (node (ref "J2") (pin "A10") (pinfunction "RX2-_A10") (pintype "passive"))
    )
    (net (code "143") (name "unconnected-(J2-SBU1-PadA8)") (class "Default")
      (node (ref "J2") (pin "A8") (pinfunction "SBU1_A8") (pintype "passive"))
    )
    (net (code "144") (name "unconnected-(J2-SBU2-PadB8)") (class "Default")
      (node (ref "J2") (pin "B8") (pinfunction "SBU2_B8") (pintype "passive"))
    )
    (net (code "145") (name "unconnected-(J2-TX1+-PadA2)") (class "Default")
      (node (ref "J2") (pin "A2") (pinfunction "TX1+_A2") (pintype "passive"))
    )
    (net (code "146") (name "unconnected-(J2-TX1--PadA3)") (class "Default")
      (node (ref "J2") (pin "A3") (pinfunction "TX1-_A3") (pintype "passive"))
    )
    (net (code "147") (name "unconnected-(J2-TX2+-PadB2)") (class "Default")
      (node (ref "J2") (pin "B2") (pinfunction "TX2+_B2") (pintype "passive"))
    )
    (net (code "148") (name "unconnected-(J2-VBUS_A4-PadA4)") (class "Default")
      (node (ref "J2") (pin "A4") (pinfunction "VBUS_A4_A4") (pintype "passive"))
    )
    (net (code "149") (name "unconnected-(J2-VBUS_A9-PadA9)") (class "Default")
      (node (ref "J2") (pin "A9") (pinfunction "VBUS_A9_A9") (pintype "passive"))
    )
    (net (code "150") (name "unconnected-(J2-VBUS_B4-PadB4)") (class "Default")
      (node (ref "J2") (pin "B4") (pinfunction "VBUS_B4_B4") (pintype "passive"))
    )
    (net (code "151") (name "unconnected-(J2-VBUS_B9-PadB9)") (class "Default")
      (node (ref "J2") (pin "B9") (pinfunction "VBUS_B9_B9") (pintype "passive"))
    )
    (net (code "152") (name "unconnected-(U1-QH*-Pad9)") (class "Default")
      (node (ref "U1") (pin "9") (pinfunction "QH*_9") (pintype "tri_state"))
    )
    (net (code "153") (name "unconnected-(U2-N.C.-Pad44)") (class "Default")
      (node (ref "U2") (pin "44") (pinfunction "N.C._44") (pintype "no_connect"))
    )
    (net (code "154") (name "unconnected-(U2-P0.23-Pad28)") (class "Default")
      (node (ref "U2") (pin "28") (pinfunction "P0.23_28") (pintype "bidirectional"))
    )
    (net (code "155") (name "unconnected-(U4-IN2A-Pad20)") (class "Default")
      (node (ref "U4") (pin "20") (pinfunction "IN2A_20") (pintype "input"))
    )
    (net (code "156") (name "unconnected-(U4-IN2B-Pad19)") (class "Default")
      (node (ref "U4") (pin "19") (pinfunction "IN2B_19") (pintype "input"))
    )
    (net (code "157") (name "unconnected-(U4-OUT2A-Pad3)") (class "Default")
      (node (ref "U4") (pin "3") (pinfunction "OUT2A_3") (pintype "output"))
    )
    (net (code "158") (name "unconnected-(U4-OUT2B-Pad16)") (class "Default")
      (node (ref "U4") (pin "16") (pinfunction "OUT2B_16") (pintype "output"))
    )
    (net (code "159") (name "unconnected-(U5-GPIO.0{slash}TXT-Pad14)") (class "Default")
      (node (ref "U5") (pin "14") (pinfunction "GPIO.0/TXT_14") (pintype "bidirectional"))
    )
    (net (code "160") (name "unconnected-(U5-GPIO.1{slash}RXT-Pad13)") (class "Default")
      (node (ref "U5") (pin "13") (pinfunction "GPIO.1/RXT_13") (pintype "bidirectional"))
    )
    (net (code "161") (name "unconnected-(U5-GPIO.2{slash}RS485-Pad12)") (class "Default")
      (node (ref "U5") (pin "12") (pinfunction "GPIO.2/RS485_12") (pintype "bidirectional"))
    )
    (net (code "162") (name "unconnected-(U5-GPIO.3{slash}WAKEUP-Pad11)") (class "Default")
      (node (ref "U5") (pin "11") (pinfunction "GPIO.3/WAKEUP_11") (pintype "bidirectional"))
    )
    (net (code "163") (name "unconnected-(U5-SUSPENDB-Pad15)") (class "Default")
      (node (ref "U5") (pin "15") (pinfunction "SUSPENDB_15") (pintype "output"))
    )
    (net (code "164") (name "unconnected-(U5-~{CTS}-Pad18)") (class "Default")
      (node (ref "U5") (pin "18") (pinfunction "~{CTS}_18") (pintype "input"))
    )
    (net (code "165") (name "unconnected-(U5-~{DCD}-Pad24)") (class "Default")
      (node (ref "U5") (pin "24") (pinfunction "~{DCD}_24") (pintype "input"))
    )
    (net (code "166") (name "unconnected-(U5-~{DSR}-Pad22)") (class "Default")
      (node (ref "U5") (pin "22") (pinfunction "~{DSR}_22") (pintype "input"))
    )
    (net (code "167") (name "unconnected-(U5-~{DTR}-Pad23)") (class "Default")
      (node (ref "U5") (pin "23") (pinfunction "~{DTR}_23") (pintype "output"))
    )
    (net (code "168") (name "unconnected-(U5-~{RI}{slash}CLK-Pad1)") (class "Default")
      (node (ref "U5") (pin "1") (pinfunction "~{RI}/CLK_1") (pintype "bidirectional"))
    )
    (net (code "169") (name "unconnected-(U5-~{RTS}-Pad19)") (class "Default")
      (node (ref "U5") (pin "19") (pinfunction "~{RTS}_19") (pintype "output"))
    )
  )
)
